# Sheet1.net
KiCad netlist of a schematic drawn in Altium Designer
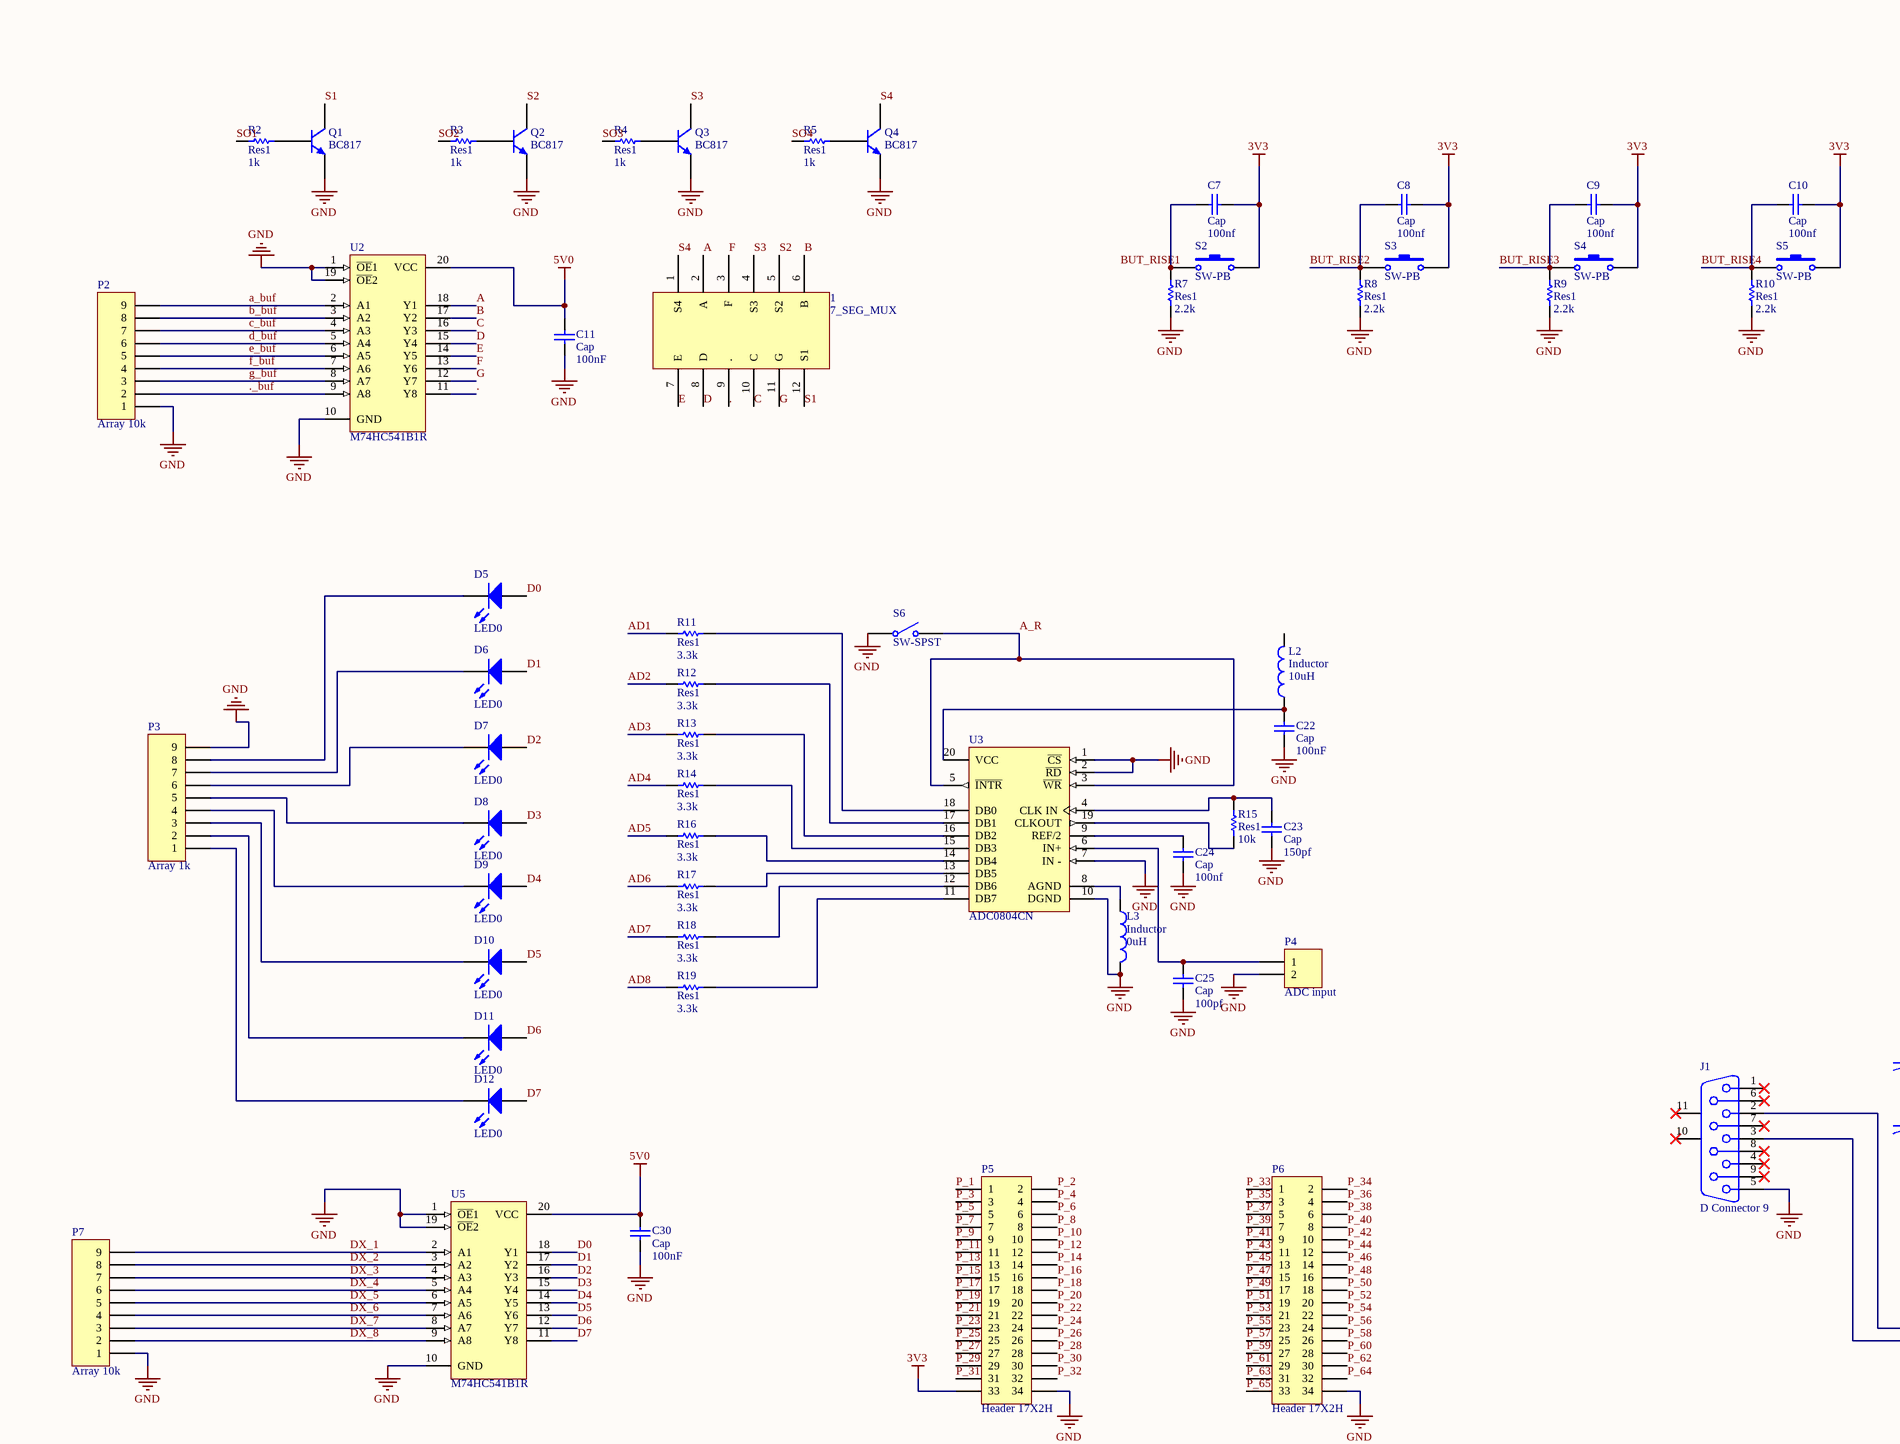
[diagram p0: Sheet1.SchDoc, top left]
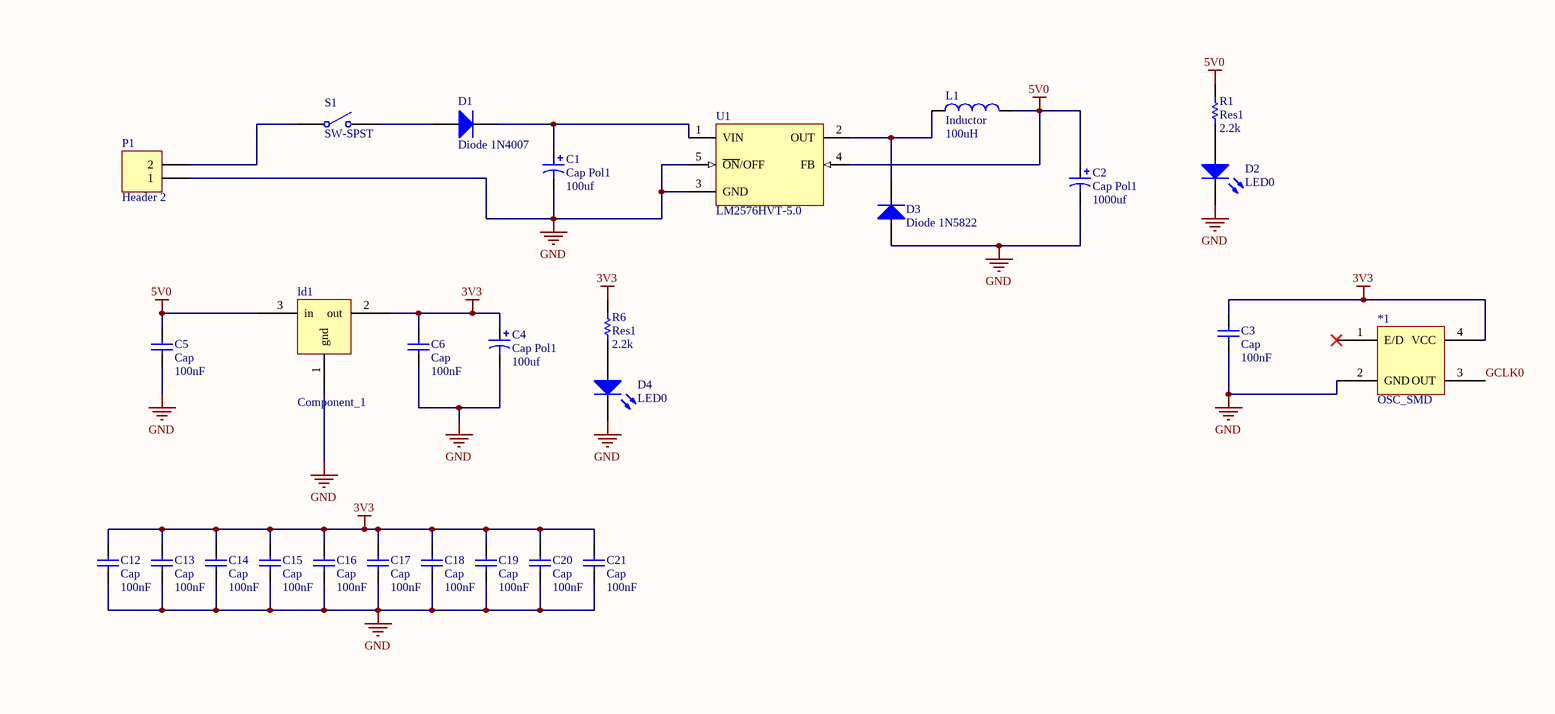
[diagram p1: Sheet1.SchDoc, top right]
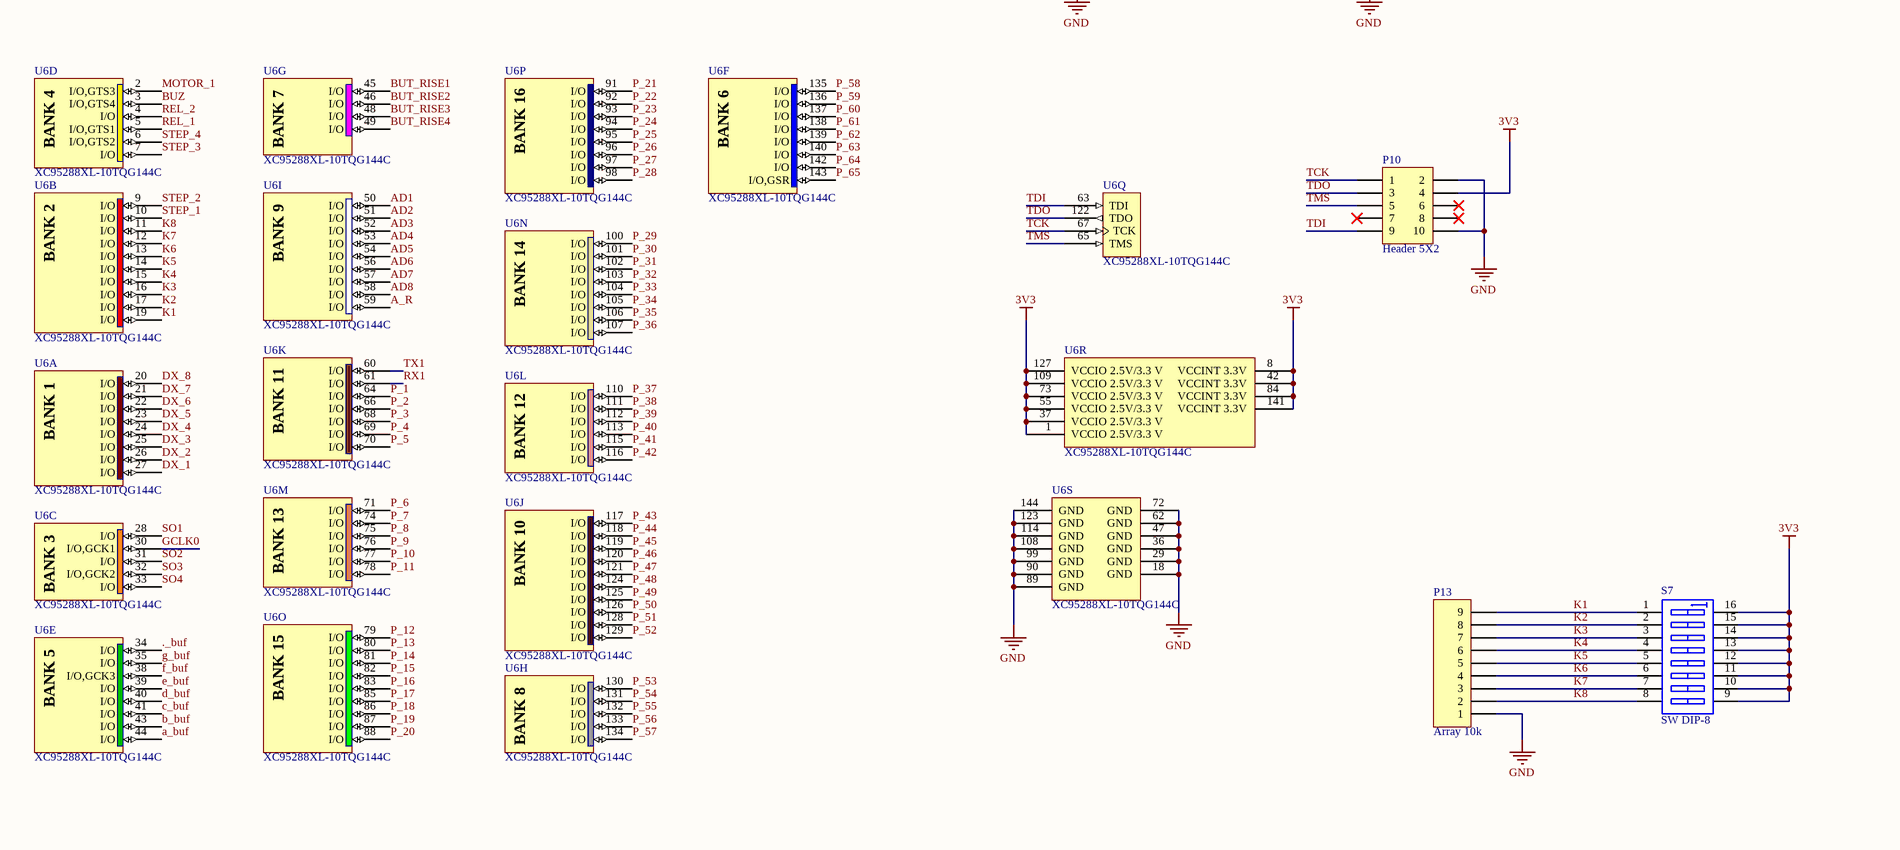
[diagram p2: Sheet1.SchDoc, bottom left]
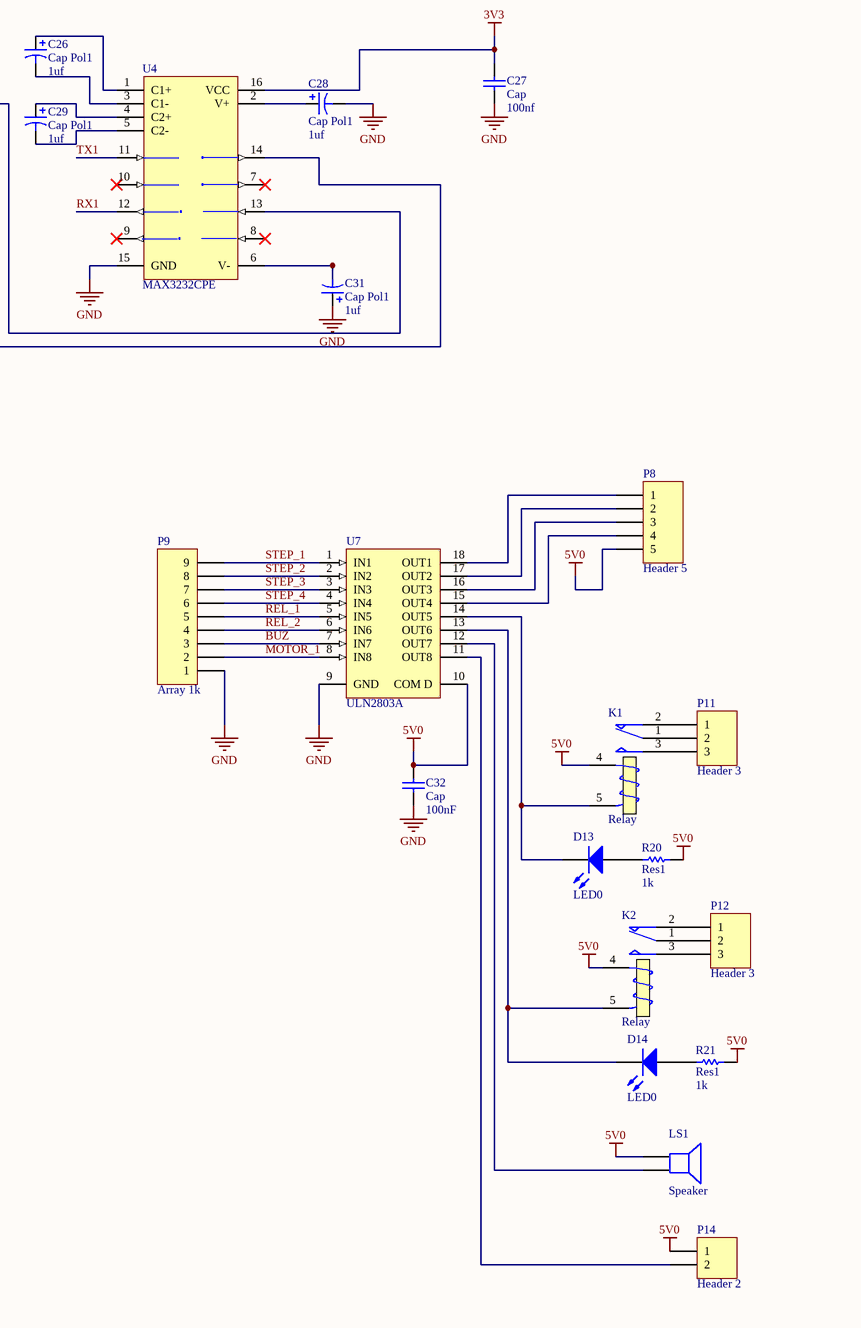
[diagram p3: Sheet1.SchDoc, bottom right]

(export (version "E")
  (design (tool "Eeschema 10.0.6"))
  (components
    (comp (ref "*1") (value "OSC_SMD") (footprint "osc_smd") (libsource (lib "OSC_SMD") (part "Component_1")))
    (comp (ref "1")
      (value "7_SEG_MUX")
      (footprint "s7_mux")
      (libsource (lib "7_SEG_MUX") (part "Component_1"))
    )
    (comp (ref "C1")
      (value "Cap Pol1")
      (footprint "C_CYL_SMD2")
      (description "Polarized Capacitor (Radial)")
      (fields (field (name "ALTIUM_VALUE") "100uf") (field (name "PUBLISHER") "Altium Limited"))
      (libsource (lib "Miscellaneous Devices") (part "Cap Pol1"))
    )
    (comp (ref "C2")
      (value "Cap Pol1")
      (footprint "C_CYL_SMD")
      (description "Polarized Capacitor (Radial)")
      (fields (field (name "ALTIUM_VALUE") "1000uf") (field (name "PUBLISHER") "Altium Limited"))
      (libsource (lib "Miscellaneous Devices") (part "Cap Pol1"))
    )
    (comp (ref "C3")
      (value "Cap")
      (footprint "SMD_805")
      (description "Capacitor")
      (fields (field (name "ALTIUM_VALUE") "100nF") (field (name "PUBLISHER") "Altium Limited"))
      (libsource (lib "Miscellaneous Devices") (part "Cap"))
    )
    (comp (ref "C4")
      (value "Cap Pol1")
      (footprint "C_B")
      (description "Polarized Capacitor (Radial)")
      (fields (field (name "ALTIUM_VALUE") "100uf") (field (name "PUBLISHER") "Altium Limited"))
      (libsource (lib "Miscellaneous Devices") (part "Cap Pol1"))
    )
    (comp (ref "C5")
      (value "Cap")
      (footprint "SMD_805")
      (description "Capacitor")
      (fields (field (name "ALTIUM_VALUE") "100nF") (field (name "PUBLISHER") "Altium Limited"))
      (libsource (lib "Miscellaneous Devices") (part "Cap"))
    )
    (comp (ref "C6")
      (value "Cap")
      (footprint "SMD_805")
      (description "Capacitor")
      (fields (field (name "ALTIUM_VALUE") "100nF") (field (name "PUBLISHER") "Altium Limited"))
      (libsource (lib "Miscellaneous Devices") (part "Cap"))
    )
    (comp (ref "C7")
      (value "Cap")
      (footprint "SMD_805")
      (description "Capacitor")
      (fields (field (name "ALTIUM_VALUE") "100nf") (field (name "PUBLISHER") "Altium Limited"))
      (libsource (lib "Miscellaneous Devices") (part "Cap"))
    )
    (comp (ref "C8")
      (value "Cap")
      (footprint "SMD_805")
      (description "Capacitor")
      (fields (field (name "ALTIUM_VALUE") "100nf") (field (name "PUBLISHER") "Altium Limited"))
      (libsource (lib "Miscellaneous Devices") (part "Cap"))
    )
    (comp (ref "C9")
      (value "Cap")
      (footprint "SMD_805")
      (description "Capacitor")
      (fields (field (name "ALTIUM_VALUE") "100nf") (field (name "PUBLISHER") "Altium Limited"))
      (libsource (lib "Miscellaneous Devices") (part "Cap"))
    )
    (comp (ref "C10")
      (value "Cap")
      (footprint "SMD_805")
      (description "Capacitor")
      (fields (field (name "ALTIUM_VALUE") "100nf") (field (name "PUBLISHER") "Altium Limited"))
      (libsource (lib "Miscellaneous Devices") (part "Cap"))
    )
    (comp (ref "C11")
      (value "Cap")
      (footprint "SMD_805")
      (description "Capacitor")
      (fields (field (name "ALTIUM_VALUE") "100nF") (field (name "PUBLISHER") "Altium Limited"))
      (libsource (lib "Miscellaneous Devices") (part "Cap"))
    )
    (comp (ref "C12")
      (value "Cap")
      (footprint "SMD_805")
      (description "Capacitor")
      (fields (field (name "ALTIUM_VALUE") "100nF") (field (name "PUBLISHER") "Altium Limited"))
      (libsource (lib "Miscellaneous Devices") (part "Cap"))
    )
    (comp (ref "C13")
      (value "Cap")
      (footprint "SMD_805")
      (description "Capacitor")
      (fields (field (name "ALTIUM_VALUE") "100nF") (field (name "PUBLISHER") "Altium Limited"))
      (libsource (lib "Miscellaneous Devices") (part "Cap"))
    )
    (comp (ref "C14")
      (value "Cap")
      (footprint "SMD_805")
      (description "Capacitor")
      (fields (field (name "ALTIUM_VALUE") "100nF") (field (name "PUBLISHER") "Altium Limited"))
      (libsource (lib "Miscellaneous Devices") (part "Cap"))
    )
    (comp (ref "C15")
      (value "Cap")
      (footprint "SMD_805")
      (description "Capacitor")
      (fields (field (name "ALTIUM_VALUE") "100nF") (field (name "PUBLISHER") "Altium Limited"))
      (libsource (lib "Miscellaneous Devices") (part "Cap"))
    )
    (comp (ref "C16")
      (value "Cap")
      (footprint "SMD_805")
      (description "Capacitor")
      (fields (field (name "ALTIUM_VALUE") "100nF") (field (name "PUBLISHER") "Altium Limited"))
      (libsource (lib "Miscellaneous Devices") (part "Cap"))
    )
    (comp (ref "C17")
      (value "Cap")
      (footprint "SMD_805")
      (description "Capacitor")
      (fields (field (name "ALTIUM_VALUE") "100nF") (field (name "PUBLISHER") "Altium Limited"))
      (libsource (lib "Miscellaneous Devices") (part "Cap"))
    )
    (comp (ref "C18")
      (value "Cap")
      (footprint "SMD_805")
      (description "Capacitor")
      (fields (field (name "ALTIUM_VALUE") "100nF") (field (name "PUBLISHER") "Altium Limited"))
      (libsource (lib "Miscellaneous Devices") (part "Cap"))
    )
    (comp (ref "C19")
      (value "Cap")
      (footprint "SMD_805")
      (description "Capacitor")
      (fields (field (name "ALTIUM_VALUE") "100nF") (field (name "PUBLISHER") "Altium Limited"))
      (libsource (lib "Miscellaneous Devices") (part "Cap"))
    )
    (comp (ref "C20")
      (value "Cap")
      (footprint "SMD_805")
      (description "Capacitor")
      (fields (field (name "ALTIUM_VALUE") "100nF") (field (name "PUBLISHER") "Altium Limited"))
      (libsource (lib "Miscellaneous Devices") (part "Cap"))
    )
    (comp (ref "C21")
      (value "Cap")
      (footprint "SMD_805")
      (description "Capacitor")
      (fields (field (name "ALTIUM_VALUE") "100nF") (field (name "PUBLISHER") "Altium Limited"))
      (libsource (lib "Miscellaneous Devices") (part "Cap"))
    )
    (comp (ref "C22")
      (value "Cap")
      (footprint "SMD_805")
      (description "Capacitor")
      (fields (field (name "ALTIUM_VALUE") "100nF") (field (name "PUBLISHER") "Altium Limited"))
      (libsource (lib "Miscellaneous Devices") (part "Cap"))
    )
    (comp (ref "C23")
      (value "Cap")
      (footprint "SMD_805")
      (description "Capacitor")
      (fields (field (name "ALTIUM_VALUE") "150pf") (field (name "PUBLISHER") "Altium Limited"))
      (libsource (lib "Miscellaneous Devices") (part "Cap"))
    )
    (comp (ref "C24")
      (value "Cap")
      (footprint "SMD_805")
      (description "Capacitor")
      (fields (field (name "ALTIUM_VALUE") "100nf") (field (name "PUBLISHER") "Altium Limited"))
      (libsource (lib "Miscellaneous Devices") (part "Cap"))
    )
    (comp (ref "C25")
      (value "Cap")
      (footprint "SMD_805")
      (description "Capacitor")
      (fields (field (name "ALTIUM_VALUE") "100pf") (field (name "PUBLISHER") "Altium Limited"))
      (libsource (lib "Miscellaneous Devices") (part "Cap"))
    )
    (comp (ref "C26")
      (value "Cap Pol1")
      (footprint "c_b")
      (description "Polarized Capacitor (Radial)")
      (fields (field (name "ALTIUM_VALUE") "1uf") (field (name "PUBLISHER") "Altium Limited"))
      (libsource (lib "Miscellaneous Devices") (part "Cap Pol1"))
    )
    (comp (ref "C27")
      (value "Cap")
      (footprint "SMD_805")
      (description "Capacitor")
      (fields (field (name "ALTIUM_VALUE") "100nf") (field (name "PUBLISHER") "Altium Limited"))
      (libsource (lib "Miscellaneous Devices") (part "Cap"))
    )
    (comp (ref "C28")
      (value "Cap Pol1")
      (footprint "c_b")
      (description "Polarized Capacitor (Radial)")
      (fields (field (name "ALTIUM_VALUE") "1uf") (field (name "PUBLISHER") "Altium Limited"))
      (libsource (lib "Miscellaneous Devices") (part "Cap Pol1"))
    )
    (comp (ref "C29")
      (value "Cap Pol1")
      (footprint "c_b")
      (description "Polarized Capacitor (Radial)")
      (fields (field (name "ALTIUM_VALUE") "1uf") (field (name "PUBLISHER") "Altium Limited"))
      (libsource (lib "Miscellaneous Devices") (part "Cap Pol1"))
    )
    (comp (ref "C30")
      (value "Cap")
      (footprint "SMD_805")
      (description "Capacitor")
      (fields (field (name "ALTIUM_VALUE") "100nF") (field (name "PUBLISHER") "Altium Limited"))
      (libsource (lib "Miscellaneous Devices") (part "Cap"))
    )
    (comp (ref "C31")
      (value "Cap Pol1")
      (footprint "c_b")
      (description "Polarized Capacitor (Radial)")
      (fields (field (name "ALTIUM_VALUE") "1uf") (field (name "PUBLISHER") "Altium Limited"))
      (libsource (lib "") (part "Cap Pol1_1"))
    )
    (comp (ref "C32")
      (value "Cap")
      (footprint "SMD_805")
      (description "Capacitor")
      (fields (field (name "ALTIUM_VALUE") "100nF") (field (name "PUBLISHER") "Altium Limited"))
      (libsource (lib "Miscellaneous Devices") (part "Cap"))
    )
    (comp (ref "D1")
      (value "Diode 1N4007")
      (footprint "TVS")
      (description "1 Amp General Purpose Rectifier")
      (fields (field (name "PUBLISHER") "Altium Limited"))
      (libsource (lib "Miscellaneous Devices") (part "Diode 1N4007"))
    )
    (comp (ref "D2")
      (value "LED0")
      (footprint "SMD_805")
      (description "Typical INFRARED GaAs LED")
      (fields (field (name "PUBLISHER") "Altium Limited"))
      (libsource (lib "Miscellaneous Devices") (part "LED0"))
    )
    (comp (ref "D3")
      (value "Diode 1N5822")
      (footprint "1N5822")
      (description "1 Amp General Purpose Rectifier")
      (fields (field (name "PUBLISHER") "Altium Limited"))
      (libsource (lib "Miscellaneous Devices") (part "Diode 1N4007"))
    )
    (comp (ref "D4")
      (value "LED0")
      (footprint "SMD_805")
      (description "Typical INFRARED GaAs LED")
      (fields (field (name "PUBLISHER") "Altium Limited"))
      (libsource (lib "Miscellaneous Devices") (part "LED0"))
    )
    (comp (ref "D5")
      (value "LED0")
      (footprint "SMD_805")
      (description "Typical INFRARED GaAs LED")
      (fields (field (name "PUBLISHER") "Altium Limited"))
      (libsource (lib "Miscellaneous Devices") (part "LED0"))
    )
    (comp (ref "D6")
      (value "LED0")
      (footprint "SMD_805")
      (description "Typical INFRARED GaAs LED")
      (fields (field (name "PUBLISHER") "Altium Limited"))
      (libsource (lib "Miscellaneous Devices") (part "LED0"))
    )
    (comp (ref "D7")
      (value "LED0")
      (footprint "SMD_805")
      (description "Typical INFRARED GaAs LED")
      (fields (field (name "PUBLISHER") "Altium Limited"))
      (libsource (lib "Miscellaneous Devices") (part "LED0"))
    )
    (comp (ref "D8")
      (value "LED0")
      (footprint "SMD_805")
      (description "Typical INFRARED GaAs LED")
      (fields (field (name "PUBLISHER") "Altium Limited"))
      (libsource (lib "Miscellaneous Devices") (part "LED0"))
    )
    (comp (ref "D9")
      (value "LED0")
      (footprint "SMD_805")
      (description "Typical INFRARED GaAs LED")
      (fields (field (name "PUBLISHER") "Altium Limited"))
      (libsource (lib "Miscellaneous Devices") (part "LED0"))
    )
    (comp (ref "D10")
      (value "LED0")
      (footprint "SMD_805")
      (description "Typical INFRARED GaAs LED")
      (fields (field (name "PUBLISHER") "Altium Limited"))
      (libsource (lib "Miscellaneous Devices") (part "LED0"))
    )
    (comp (ref "D11")
      (value "LED0")
      (footprint "SMD_805")
      (description "Typical INFRARED GaAs LED")
      (fields (field (name "PUBLISHER") "Altium Limited"))
      (libsource (lib "Miscellaneous Devices") (part "LED0"))
    )
    (comp (ref "D12")
      (value "LED0")
      (footprint "SMD_805")
      (description "Typical INFRARED GaAs LED")
      (fields (field (name "PUBLISHER") "Altium Limited"))
      (libsource (lib "Miscellaneous Devices") (part "LED0"))
    )
    (comp (ref "D13")
      (value "LED0")
      (footprint "SMD_805")
      (description "Typical INFRARED GaAs LED")
      (fields (field (name "PUBLISHER") "Altium Limited"))
      (libsource (lib "Miscellaneous Devices") (part "LED0"))
    )
    (comp (ref "D14")
      (value "LED0")
      (footprint "SMD_805")
      (description "Typical INFRARED GaAs LED")
      (fields (field (name "PUBLISHER") "Altium Limited"))
      (libsource (lib "Miscellaneous Devices") (part "LED0"))
    )
    (comp (ref "J1")
      (value "D Connector 9")
      (footprint "com")
      (description "Receptacle Assembly, 9 Position, Right Angle")
      (fields (field (name "PUBLISHER") "Altium Limited"))
      (libsource (lib "Miscellaneous Connectors") (part "D Connector 9"))
    )
    (comp (ref "K1")
      (value "Relay")
      (footprint "relay_5v")
      (description "SPDT Relay")
      (fields (field (name "PUBLISHER") "Altium Limited"))
      (libsource (lib "Miscellaneous Devices") (part "Relay"))
    )
    (comp (ref "K2")
      (value "Relay")
      (footprint "relay_5v")
      (description "SPDT Relay")
      (fields (field (name "PUBLISHER") "Altium Limited"))
      (libsource (lib "Miscellaneous Devices") (part "Relay"))
    )
    (comp (ref "L1")
      (value "Inductor")
      (footprint "INDUC_SMD")
      (fields (field (name "ALTIUM_VALUE") "100uH") (field (name "PUBLISHER") "Altium Limited"))
      (libsource (lib "Miscellaneous Devices") (part "Inductor"))
    )
    (comp (ref "L2")
      (value "Inductor")
      (footprint "SMD_805")
      (fields (field (name "ALTIUM_VALUE") "10uH") (field (name "PUBLISHER") "Altium Limited"))
      (libsource (lib "Miscellaneous Devices") (part "Inductor"))
    )
    (comp (ref "L3")
      (value "Inductor")
      (footprint "SMD_805")
      (fields (field (name "ALTIUM_VALUE") "0uH") (field (name "PUBLISHER") "Altium Limited"))
      (libsource (lib "Miscellaneous Devices") (part "Inductor"))
    )
    (comp (ref "ld1")
      (value "Component_1")
      (footprint "SOT223")
      (libsource (lib "lm1117") (part "Component_1"))
    )
    (comp (ref "LS1")
      (value "Speaker")
      (footprint "buzzer")
      (description "Loudspeaker")
      (fields (field (name "PUBLISHER") "Altium Limited"))
      (libsource (lib "Miscellaneous Devices") (part "Speaker"))
    )
    (comp (ref "P1")
      (value "Header 2")
      (footprint "ADAP_JACK")
      (description "Header, 2-Pin")
      (fields (field (name "PUBLISHER") "Altium Limited"))
      (libsource (lib "Miscellaneous Connectors") (part "Header 2"))
    )
    (comp (ref "P2")
      (value "Array 10k")
      (footprint "aray 9")
      (description "Header, 9-Pin, Right Angle")
      (fields (field (name "PUBLISHER") "Altium Limited"))
      (libsource (lib "Miscellaneous Connectors") (part "Header 9H"))
    )
    (comp (ref "P3")
      (value "Array 1k")
      (footprint "Aray 9")
      (description "Header, 9-Pin, Right Angle")
      (fields (field (name "PUBLISHER") "Altium Limited"))
      (libsource (lib "Miscellaneous Connectors") (part "Header 9H"))
    )
    (comp (ref "P4")
      (value "ADC input")
      (footprint "pin_2_w")
      (description "Header, 2-Pin")
      (fields (field (name "PUBLISHER") "Altium Limited"))
      (libsource (lib "") (part "Header 2_1"))
    )
    (comp (ref "P5")
      (value "Header 17X2H")
      (footprint "HDR2X17H")
      (description "Header, 17-Pin, Dual row, Right Angle")
      (fields (field (name "PUBLISHER") "Altium Limited"))
      (libsource (lib "Miscellaneous Connectors") (part "Header 17X2H"))
    )
    (comp (ref "P6")
      (value "Header 17X2H")
      (footprint "HDR2X17H")
      (description "Header, 17-Pin, Dual row, Right Angle")
      (fields (field (name "PUBLISHER") "Altium Limited"))
      (libsource (lib "Miscellaneous Connectors") (part "Header 17X2H"))
    )
    (comp (ref "P7")
      (value "Array 10k")
      (footprint "aray 9")
      (description "Header, 9-Pin, Right Angle")
      (fields (field (name "PUBLISHER") "Altium Limited"))
      (libsource (lib "Miscellaneous Connectors") (part "Header 9H"))
    )
    (comp (ref "P8")
      (value "Header 5")
      (footprint "pin_5_w")
      (description "Header, 5-Pin")
      (fields (field (name "PUBLISHER") "Altium Limited"))
      (libsource (lib "Miscellaneous Connectors") (part "Header 5"))
    )
    (comp (ref "P9")
      (value "Array 1k")
      (footprint "aray 9")
      (description "Header, 9-Pin, Right Angle")
      (fields (field (name "PUBLISHER") "Altium Limited"))
      (libsource (lib "Miscellaneous Connectors") (part "Header 9H"))
    )
    (comp (ref "P10")
      (value "Header 5X2")
      (footprint "box2x5_3d")
      (description "Header, 5-Pin, Dual row")
      (fields (field (name "PUBLISHER") "Altium Limited"))
      (libsource (lib "Miscellaneous Connectors") (part "Header 5X2"))
    )
    (comp (ref "P11")
      (value "Header 3")
      (footprint "pin_3_w")
      (description "Header, 3-Pin")
      (fields (field (name "PUBLISHER") "Altium Limited"))
      (libsource (lib "Miscellaneous Connectors") (part "Header 3"))
    )
    (comp (ref "P12")
      (value "Header 3")
      (footprint "pin_3_w")
      (description "Header, 3-Pin")
      (fields (field (name "PUBLISHER") "Altium Limited"))
      (libsource (lib "Miscellaneous Connectors") (part "Header 3"))
    )
    (comp (ref "P13")
      (value "Array 10k")
      (footprint "aray 9")
      (description "Header, 9-Pin, Right Angle")
      (fields (field (name "PUBLISHER") "Altium Limited"))
      (libsource (lib "Miscellaneous Connectors") (part "Header 9H"))
    )
    (comp (ref "P14")
      (value "Header 2")
      (footprint "pin_2_w")
      (description "Header, 2-Pin")
      (fields (field (name "PUBLISHER") "Altium Limited"))
      (libsource (lib "") (part "Header 2_1"))
    )
    (comp (ref "Q1")
      (value "BC817")
      (footprint "sot23")
      (description "NPN General Purpose Amplifier")
      (fields (field (name "PUBLISHER") "Altium Limited"))
      (libsource (lib "Miscellaneous Devices") (part "2N3904"))
    )
    (comp (ref "Q2")
      (value "BC817")
      (footprint "sot23")
      (description "NPN General Purpose Amplifier")
      (fields (field (name "PUBLISHER") "Altium Limited"))
      (libsource (lib "Miscellaneous Devices") (part "2N3904"))
    )
    (comp (ref "Q3")
      (value "BC817")
      (footprint "sot23")
      (description "NPN General Purpose Amplifier")
      (fields (field (name "PUBLISHER") "Altium Limited"))
      (libsource (lib "Miscellaneous Devices") (part "2N3904"))
    )
    (comp (ref "Q4")
      (value "BC817")
      (footprint "sot23")
      (description "NPN General Purpose Amplifier")
      (fields (field (name "PUBLISHER") "Altium Limited"))
      (libsource (lib "Miscellaneous Devices") (part "2N3904"))
    )
    (comp (ref "R1")
      (value "Res1")
      (footprint "SMD_805")
      (description "Resistor")
      (fields (field (name "ALTIUM_VALUE") "2.2k") (field (name "PUBLISHER") "Altium Limited"))
      (libsource (lib "Miscellaneous Devices") (part "Res1"))
    )
    (comp (ref "R2")
      (value "Res1")
      (footprint "SMD_805")
      (description "Resistor")
      (fields (field (name "ALTIUM_VALUE") "1k") (field (name "PUBLISHER") "Altium Limited"))
      (libsource (lib "Miscellaneous Devices") (part "Res1"))
    )
    (comp (ref "R3")
      (value "Res1")
      (footprint "SMD_805")
      (description "Resistor")
      (fields (field (name "ALTIUM_VALUE") "1k") (field (name "PUBLISHER") "Altium Limited"))
      (libsource (lib "Miscellaneous Devices") (part "Res1"))
    )
    (comp (ref "R4")
      (value "Res1")
      (footprint "SMD_805")
      (description "Resistor")
      (fields (field (name "ALTIUM_VALUE") "1k") (field (name "PUBLISHER") "Altium Limited"))
      (libsource (lib "Miscellaneous Devices") (part "Res1"))
    )
    (comp (ref "R5")
      (value "Res1")
      (footprint "SMD_805")
      (description "Resistor")
      (fields (field (name "ALTIUM_VALUE") "1k") (field (name "PUBLISHER") "Altium Limited"))
      (libsource (lib "Miscellaneous Devices") (part "Res1"))
    )
    (comp (ref "R6")
      (value "Res1")
      (footprint "SMD_805")
      (description "Resistor")
      (fields (field (name "ALTIUM_VALUE") "2.2k") (field (name "PUBLISHER") "Altium Limited"))
      (libsource (lib "Miscellaneous Devices") (part "Res1"))
    )
    (comp (ref "R7")
      (value "Res1")
      (footprint "SMD_805")
      (description "Resistor")
      (fields (field (name "ALTIUM_VALUE") "2.2k") (field (name "PUBLISHER") "Altium Limited"))
      (libsource (lib "Miscellaneous Devices") (part "Res1"))
    )
    (comp (ref "R8")
      (value "Res1")
      (footprint "SMD_805")
      (description "Resistor")
      (fields (field (name "ALTIUM_VALUE") "2.2k") (field (name "PUBLISHER") "Altium Limited"))
      (libsource (lib "Miscellaneous Devices") (part "Res1"))
    )
    (comp (ref "R9")
      (value "Res1")
      (footprint "SMD_805")
      (description "Resistor")
      (fields (field (name "ALTIUM_VALUE") "2.2k") (field (name "PUBLISHER") "Altium Limited"))
      (libsource (lib "Miscellaneous Devices") (part "Res1"))
    )
    (comp (ref "R10")
      (value "Res1")
      (footprint "SMD_805")
      (description "Resistor")
      (fields (field (name "ALTIUM_VALUE") "2.2k") (field (name "PUBLISHER") "Altium Limited"))
      (libsource (lib "Miscellaneous Devices") (part "Res1"))
    )
    (comp (ref "R11")
      (value "Res1")
      (footprint "SMD_805")
      (description "Resistor")
      (fields (field (name "ALTIUM_VALUE") "3.3k") (field (name "PUBLISHER") "Altium Limited"))
      (libsource (lib "Miscellaneous Devices") (part "Res1"))
    )
    (comp (ref "R12")
      (value "Res1")
      (footprint "SMD_805")
      (description "Resistor")
      (fields (field (name "ALTIUM_VALUE") "3.3k") (field (name "PUBLISHER") "Altium Limited"))
      (libsource (lib "Miscellaneous Devices") (part "Res1"))
    )
    (comp (ref "R13")
      (value "Res1")
      (footprint "SMD_805")
      (description "Resistor")
      (fields (field (name "ALTIUM_VALUE") "3.3k") (field (name "PUBLISHER") "Altium Limited"))
      (libsource (lib "Miscellaneous Devices") (part "Res1"))
    )
    (comp (ref "R14")
      (value "Res1")
      (footprint "SMD_805")
      (description "Resistor")
      (fields (field (name "ALTIUM_VALUE") "3.3k") (field (name "PUBLISHER") "Altium Limited"))
      (libsource (lib "Miscellaneous Devices") (part "Res1"))
    )
    (comp (ref "R15")
      (value "Res1")
      (footprint "SMD_805")
      (description "Resistor")
      (fields (field (name "ALTIUM_VALUE") "10k") (field (name "PUBLISHER") "Altium Limited"))
      (libsource (lib "Miscellaneous Devices") (part "Res1"))
    )
    (comp (ref "R16")
      (value "Res1")
      (footprint "SMD_805")
      (description "Resistor")
      (fields (field (name "ALTIUM_VALUE") "3.3k") (field (name "PUBLISHER") "Altium Limited"))
      (libsource (lib "Miscellaneous Devices") (part "Res1"))
    )
    (comp (ref "R17")
      (value "Res1")
      (footprint "SMD_805")
      (description "Resistor")
      (fields (field (name "ALTIUM_VALUE") "3.3k") (field (name "PUBLISHER") "Altium Limited"))
      (libsource (lib "Miscellaneous Devices") (part "Res1"))
    )
    (comp (ref "R18")
      (value "Res1")
      (footprint "SMD_805")
      (description "Resistor")
      (fields (field (name "ALTIUM_VALUE") "3.3k") (field (name "PUBLISHER") "Altium Limited"))
      (libsource (lib "Miscellaneous Devices") (part "Res1"))
    )
    (comp (ref "R19")
      (value "Res1")
      (footprint "SMD_805")
      (description "Resistor")
      (fields (field (name "ALTIUM_VALUE") "3.3k") (field (name "PUBLISHER") "Altium Limited"))
      (libsource (lib "Miscellaneous Devices") (part "Res1"))
    )
    (comp (ref "R20")
      (value "Res1")
      (footprint "SMD_805")
      (description "Resistor")
      (fields (field (name "ALTIUM_VALUE") "1k") (field (name "PUBLISHER") "Altium Limited"))
      (libsource (lib "Miscellaneous Devices") (part "Res1"))
    )
    (comp (ref "R21")
      (value "Res1")
      (footprint "SMD_805")
      (description "Resistor")
      (fields (field (name "ALTIUM_VALUE") "1k") (field (name "PUBLISHER") "Altium Limited"))
      (libsource (lib "Miscellaneous Devices") (part "Res1"))
    )
    (comp (ref "S1")
      (value "SW-SPST")
      (footprint "KEY1")
      (description "Single-Pole, Single-Throw Switch")
      (fields (field (name "PUBLISHER") "Altium Limited"))
      (libsource (lib "Miscellaneous Devices") (part "SW-SPST"))
    )
    (comp (ref "S2")
      (value "SW-PB")
      (footprint "res_b")
      (description "Switch")
      (fields (field (name "PUBLISHER") "Altium Limited"))
      (libsource (lib "Miscellaneous Devices") (part "SW-PB"))
    )
    (comp (ref "S3")
      (value "SW-PB")
      (footprint "res_b")
      (description "Switch")
      (fields (field (name "PUBLISHER") "Altium Limited"))
      (libsource (lib "Miscellaneous Devices") (part "SW-PB"))
    )
    (comp (ref "S4")
      (value "SW-PB")
      (footprint "res_b")
      (description "Switch")
      (fields (field (name "PUBLISHER") "Altium Limited"))
      (libsource (lib "Miscellaneous Devices") (part "SW-PB"))
    )
    (comp (ref "S5")
      (value "SW-PB")
      (footprint "res_b")
      (description "Switch")
      (fields (field (name "PUBLISHER") "Altium Limited"))
      (libsource (lib "Miscellaneous Devices") (part "SW-PB"))
    )
    (comp (ref "S6")
      (value "SW-SPST")
      (footprint "key1")
      (description "Single-Pole, Single-Throw Switch")
      (fields (field (name "PUBLISHER") "Altium Limited"))
      (libsource (lib "Miscellaneous Devices") (part "SW-SPST"))
    )
    (comp (ref "S7")
      (value "SW DIP-8")
      (footprint "array_key8")
      (description "DIP Switch, 8 Position, SPST")
      (fields (field (name "PUBLISHER") "Altium Limited"))
      (libsource (lib "Miscellaneous Devices") (part "SW DIP-8"))
    )
    (comp (ref "U1")
      (value "LM2576HVT-5.0")
      (footprint "LM2576_SMD")
      (description "SIMPLE SWITCHER; 3A Step-Down Voltage Regulator")
      (fields
        (field (name "MANUFACTURER") "National Semiconductor")
        (field (name "DIGIKEYPARTNUMBER") "LM2576HVT-5.0-ND")
        (field (name "PUBLISHER") "Altium Limited")
      )
      (libsource (lib "NSC Switcher") (part "LM2576HVT-5.0"))
    )
    (comp (ref "U2")
      (value "M74HC541B1R")
      (footprint "sop20")
      (description "Octal Bus Buffer with 3 State Outputs (Non Inverted)")
      (fields (field (name "PUBLISHER") "Altium Limited"))
      (libsource (lib "ST Logic Buffer Line Driver") (part "M74HC541B1R"))
    )
    (comp (ref "U3")
      (value "ADC0804CN")
      (footprint "DIp_20p")
      (description "8-Bit Analog-to-Digital Converter with Differential Inputs")
      (fields (field (name "PUBLISHER") "Altium Limited"))
      (libsource (lib "TI Converter Analog to Digital") (part "ADC0804CN"))
    )
    (comp (ref "U4")
      (value "MAX3232CPE")
      (footprint "sop16")
      (description "3.0V TO 5.5V, Low-Power, up to 1Mbps, True RS-232 Transceiver Using Four 0.1µF External Capacitor")
      (fields (field (name "PUBLISHER") "Altium Limited"))
      (libsource (lib "Maxim Communication Transceiver") (part "MAX3232CPE"))
    )
    (comp (ref "U5")
      (value "M74HC541B1R")
      (footprint "sop20")
      (description "Octal Bus Buffer with 3 State Outputs (Non Inverted)")
      (fields (field (name "PUBLISHER") "Altium Limited"))
      (libsource (lib "ST Logic Buffer Line Driver") (part "M74HC541B1R"))
    )
    (comp (ref "U6")
      (value "XC95288XL-10TQG144C")
      (footprint "TQG144_N")
      (fields (field (name "PUBLISHER") "Altium Limited"))
      (libsource (lib "Xilinx PLD XC9500XL") (part "XC95288XL-10TQG144C"))
    )
    (comp (ref "U7")
      (value "ULN2803A")
      (footprint "sol18")
      (description "High-Voltage, High-Current Darlington Array")
      (fields (field (name "PUBLISHER") "Altium Limited"))
      (libsource (lib "Allegro Interface Darlington Driver") (part "ULN2803A"))
    )
  )
  (nets
    (net (code "1") (name "/.") (class "Default")
      (node (ref "1") (pin "9") (pinfunction "._9") (pintype "passive"))
      (node (ref "U2") (pin "11") (pinfunction "Y8_11") (pintype "tri_state"))
    )
    (net (code "2") (name "/._buf") (class "Default")
      (node (ref "P2") (pin "2") (pinfunction "2_2") (pintype "passive"))
      (node (ref "U2") (pin "9") (pinfunction "A8_9") (pintype "input"))
      (node (ref "U6") (pin "34") (pinfunction "I/O_34") (pintype "bidirectional"))
    )
    (net (code "3") (name "/A") (class "Default")
      (node (ref "1") (pin "2") (pinfunction "A_2") (pintype "passive"))
      (node (ref "U2") (pin "18") (pinfunction "Y1_18") (pintype "tri_state"))
    )
    (net (code "4") (name "/AD1") (class "Default")
      (node (ref "R11") (pin "1") (pinfunction "1_1") (pintype "passive"))
      (node (ref "U6") (pin "50") (pinfunction "I/O_50") (pintype "bidirectional"))
    )
    (net (code "5") (name "/AD2") (class "Default")
      (node (ref "R12") (pin "1") (pinfunction "1_1") (pintype "passive"))
      (node (ref "U6") (pin "51") (pinfunction "I/O_51") (pintype "bidirectional"))
    )
    (net (code "6") (name "/AD3") (class "Default")
      (node (ref "R13") (pin "1") (pinfunction "1_1") (pintype "passive"))
      (node (ref "U6") (pin "52") (pinfunction "I/O_52") (pintype "bidirectional"))
    )
    (net (code "7") (name "/AD4") (class "Default")
      (node (ref "R14") (pin "1") (pinfunction "1_1") (pintype "passive"))
      (node (ref "U6") (pin "53") (pinfunction "I/O_53") (pintype "bidirectional"))
    )
    (net (code "8") (name "/AD5") (class "Default")
      (node (ref "R16") (pin "1") (pinfunction "1_1") (pintype "passive"))
      (node (ref "U6") (pin "54") (pinfunction "I/O_54") (pintype "bidirectional"))
    )
    (net (code "9") (name "/AD6") (class "Default")
      (node (ref "R17") (pin "1") (pinfunction "1_1") (pintype "passive"))
      (node (ref "U6") (pin "56") (pinfunction "I/O_56") (pintype "bidirectional"))
    )
    (net (code "10") (name "/AD7") (class "Default")
      (node (ref "R18") (pin "1") (pinfunction "1_1") (pintype "passive"))
      (node (ref "U6") (pin "57") (pinfunction "I/O_57") (pintype "bidirectional"))
    )
    (net (code "11") (name "/AD8") (class "Default")
      (node (ref "R19") (pin "1") (pinfunction "1_1") (pintype "passive"))
      (node (ref "U6") (pin "58") (pinfunction "I/O_58") (pintype "bidirectional"))
    )
    (net (code "12") (name "/A_R") (class "Default")
      (node (ref "S6") (pin "2") (pinfunction "NO_2") (pintype "passive"))
      (node (ref "U3") (pin "3") (pinfunction "~{WR}_3") (pintype "input"))
      (node (ref "U3") (pin "5") (pinfunction "~{INTR}_5") (pintype "output"))
      (node (ref "U6") (pin "59") (pinfunction "I/O_59") (pintype "bidirectional"))
    )
    (net (code "13") (name "/B") (class "Default")
      (node (ref "1") (pin "6") (pinfunction "B_6") (pintype "passive"))
      (node (ref "U2") (pin "17") (pinfunction "Y2_17") (pintype "tri_state"))
    )
    (net (code "14") (name "/BUT_RISE1") (class "Default")
      (node (ref "U6") (pin "45") (pinfunction "I/O_45") (pintype "bidirectional"))
    )
    (net (code "15") (name "/BUT_RISE2") (class "Default")
      (node (ref "C8") (pin "1") (pinfunction "1_1") (pintype "passive"))
      (node (ref "R8") (pin "1") (pinfunction "1_1") (pintype "passive"))
      (node (ref "S3") (pin "1") (pinfunction "1_1") (pintype "passive"))
      (node (ref "U6") (pin "46") (pinfunction "I/O_46") (pintype "bidirectional"))
    )
    (net (code "16") (name "/BUT_RISE3") (class "Default")
      (node (ref "C9") (pin "1") (pinfunction "1_1") (pintype "passive"))
      (node (ref "R9") (pin "1") (pinfunction "1_1") (pintype "passive"))
      (node (ref "S4") (pin "1") (pinfunction "1_1") (pintype "passive"))
      (node (ref "U6") (pin "48") (pinfunction "I/O_48") (pintype "bidirectional"))
    )
    (net (code "17") (name "/BUT_RISE4") (class "Default")
      (node (ref "C10") (pin "1") (pinfunction "1_1") (pintype "passive"))
      (node (ref "R10") (pin "1") (pinfunction "1_1") (pintype "passive"))
      (node (ref "S5") (pin "1") (pinfunction "1_1") (pintype "passive"))
      (node (ref "U6") (pin "49") (pinfunction "I/O_49") (pintype "bidirectional"))
    )
    (net (code "18") (name "/BUZ") (class "Default")
      (node (ref "P9") (pin "3") (pinfunction "3_3") (pintype "passive"))
      (node (ref "U6") (pin "3") (pinfunction "I/O,GTS4_3") (pintype "bidirectional"))
      (node (ref "U7") (pin "7") (pinfunction "IN7_7") (pintype "input"))
    )
    (net (code "19") (name "/C") (class "Default")
      (node (ref "1") (pin "10") (pinfunction "C_10") (pintype "passive"))
      (node (ref "U2") (pin "16") (pinfunction "Y3_16") (pintype "tri_state"))
    )
    (net (code "20") (name "/D") (class "Default")
      (node (ref "1") (pin "8") (pinfunction "D_8") (pintype "passive"))
      (node (ref "U2") (pin "15") (pinfunction "Y4_15") (pintype "tri_state"))
    )
    (net (code "21") (name "/D0") (class "Default")
      (node (ref "D5") (pin "1") (pinfunction "A_1") (pintype "passive"))
      (node (ref "U5") (pin "18") (pinfunction "Y1_18") (pintype "tri_state"))
    )
    (net (code "22") (name "/D1") (class "Default")
      (node (ref "D6") (pin "1") (pinfunction "A_1") (pintype "passive"))
      (node (ref "U5") (pin "17") (pinfunction "Y2_17") (pintype "tri_state"))
    )
    (net (code "23") (name "/D2") (class "Default")
      (node (ref "D7") (pin "1") (pinfunction "A_1") (pintype "passive"))
      (node (ref "U5") (pin "16") (pinfunction "Y3_16") (pintype "tri_state"))
    )
    (net (code "24") (name "/D3") (class "Default")
      (node (ref "D8") (pin "1") (pinfunction "A_1") (pintype "passive"))
      (node (ref "U5") (pin "15") (pinfunction "Y4_15") (pintype "tri_state"))
    )
    (net (code "25") (name "/D4") (class "Default")
      (node (ref "D9") (pin "1") (pinfunction "A_1") (pintype "passive"))
      (node (ref "U5") (pin "14") (pinfunction "Y5_14") (pintype "tri_state"))
    )
    (net (code "26") (name "/D5") (class "Default")
      (node (ref "D10") (pin "1") (pinfunction "A_1") (pintype "passive"))
      (node (ref "U5") (pin "13") (pinfunction "Y6_13") (pintype "tri_state"))
    )
    (net (code "27") (name "/D6") (class "Default")
      (node (ref "D11") (pin "1") (pinfunction "A_1") (pintype "passive"))
      (node (ref "U5") (pin "12") (pinfunction "Y7_12") (pintype "tri_state"))
    )
    (net (code "28") (name "/D7") (class "Default")
      (node (ref "D12") (pin "1") (pinfunction "A_1") (pintype "passive"))
      (node (ref "U5") (pin "11") (pinfunction "Y8_11") (pintype "tri_state"))
    )
    (net (code "29") (name "/DX_1") (class "Default")
      (node (ref "P7") (pin "9") (pinfunction "9_9") (pintype "passive"))
      (node (ref "U5") (pin "2") (pinfunction "A1_2") (pintype "input"))
      (node (ref "U6") (pin "27") (pinfunction "I/O_27") (pintype "bidirectional"))
    )
    (net (code "30") (name "/DX_2") (class "Default")
      (node (ref "P7") (pin "8") (pinfunction "8_8") (pintype "passive"))
      (node (ref "U5") (pin "3") (pinfunction "A2_3") (pintype "input"))
      (node (ref "U6") (pin "26") (pinfunction "I/O_26") (pintype "bidirectional"))
    )
    (net (code "31") (name "/DX_3") (class "Default")
      (node (ref "P7") (pin "7") (pinfunction "7_7") (pintype "passive"))
      (node (ref "U5") (pin "4") (pinfunction "A3_4") (pintype "input"))
      (node (ref "U6") (pin "25") (pinfunction "I/O_25") (pintype "bidirectional"))
    )
    (net (code "32") (name "/DX_4") (class "Default")
      (node (ref "P7") (pin "6") (pinfunction "6_6") (pintype "passive"))
      (node (ref "U5") (pin "5") (pinfunction "A4_5") (pintype "input"))
      (node (ref "U6") (pin "24") (pinfunction "I/O_24") (pintype "bidirectional"))
    )
    (net (code "33") (name "/DX_5") (class "Default")
      (node (ref "P7") (pin "5") (pinfunction "5_5") (pintype "passive"))
      (node (ref "U5") (pin "6") (pinfunction "A5_6") (pintype "input"))
      (node (ref "U6") (pin "23") (pinfunction "I/O_23") (pintype "bidirectional"))
    )
    (net (code "34") (name "/DX_6") (class "Default")
      (node (ref "P7") (pin "4") (pinfunction "4_4") (pintype "passive"))
      (node (ref "U5") (pin "7") (pinfunction "A6_7") (pintype "input"))
      (node (ref "U6") (pin "22") (pinfunction "I/O_22") (pintype "bidirectional"))
    )
    (net (code "35") (name "/DX_7") (class "Default")
      (node (ref "P7") (pin "3") (pinfunction "3_3") (pintype "passive"))
      (node (ref "U5") (pin "8") (pinfunction "A7_8") (pintype "input"))
      (node (ref "U6") (pin "21") (pinfunction "I/O_21") (pintype "bidirectional"))
    )
    (net (code "36") (name "/DX_8") (class "Default")
      (node (ref "P7") (pin "2") (pinfunction "2_2") (pintype "passive"))
      (node (ref "U5") (pin "9") (pinfunction "A8_9") (pintype "input"))
      (node (ref "U6") (pin "20") (pinfunction "I/O_20") (pintype "bidirectional"))
    )
    (net (code "37") (name "/E") (class "Default")
      (node (ref "1") (pin "7") (pinfunction "E_7") (pintype "passive"))
      (node (ref "U2") (pin "14") (pinfunction "Y5_14") (pintype "tri_state"))
    )
    (net (code "38") (name "/F") (class "Default")
      (node (ref "1") (pin "3") (pinfunction "F_3") (pintype "passive"))
      (node (ref "U2") (pin "13") (pinfunction "Y6_13") (pintype "tri_state"))
    )
    (net (code "39") (name "/G") (class "Default")
      (node (ref "1") (pin "11") (pinfunction "G_11") (pintype "passive"))
      (node (ref "U2") (pin "12") (pinfunction "Y7_12") (pintype "tri_state"))
    )
    (net (code "40") (name "/GCLK0") (class "Default")
      (node (ref "*1") (pin "3") (pinfunction "OUT_3") (pintype "passive"))
      (node (ref "U6") (pin "30") (pinfunction "I/O,GCK1_30") (pintype "bidirectional"))
    )
    (net (code "41") (name "/K1") (class "Default")
      (node (ref "P13") (pin "9") (pinfunction "9_9") (pintype "passive"))
      (node (ref "S7") (pin "1") (pinfunction "A1_1") (pintype "passive"))
      (node (ref "U6") (pin "19") (pinfunction "I/O_19") (pintype "bidirectional"))
    )
    (net (code "42") (name "/K2") (class "Default")
      (node (ref "P13") (pin "8") (pinfunction "8_8") (pintype "passive"))
      (node (ref "S7") (pin "2") (pinfunction "A2_2") (pintype "passive"))
      (node (ref "U6") (pin "17") (pinfunction "I/O_17") (pintype "bidirectional"))
    )
    (net (code "43") (name "/K3") (class "Default")
      (node (ref "P13") (pin "7") (pinfunction "7_7") (pintype "passive"))
      (node (ref "S7") (pin "3") (pinfunction "A3_3") (pintype "passive"))
      (node (ref "U6") (pin "16") (pinfunction "I/O_16") (pintype "bidirectional"))
    )
    (net (code "44") (name "/K4") (class "Default")
      (node (ref "P13") (pin "6") (pinfunction "6_6") (pintype "passive"))
      (node (ref "S7") (pin "4") (pinfunction "A4_4") (pintype "passive"))
      (node (ref "U6") (pin "15") (pinfunction "I/O_15") (pintype "bidirectional"))
    )
    (net (code "45") (name "/K5") (class "Default")
      (node (ref "P13") (pin "5") (pinfunction "5_5") (pintype "passive"))
      (node (ref "S7") (pin "5") (pinfunction "A5_5") (pintype "passive"))
      (node (ref "U6") (pin "14") (pinfunction "I/O_14") (pintype "bidirectional"))
    )
    (net (code "46") (name "/K6") (class "Default")
      (node (ref "P13") (pin "4") (pinfunction "4_4") (pintype "passive"))
      (node (ref "S7") (pin "6") (pinfunction "A6_6") (pintype "passive"))
      (node (ref "U6") (pin "13") (pinfunction "I/O_13") (pintype "bidirectional"))
    )
    (net (code "47") (name "/K7") (class "Default")
      (node (ref "P13") (pin "3") (pinfunction "3_3") (pintype "passive"))
      (node (ref "S7") (pin "7") (pinfunction "A7_7") (pintype "passive"))
      (node (ref "U6") (pin "12") (pinfunction "I/O_12") (pintype "bidirectional"))
    )
    (net (code "48") (name "/K8") (class "Default")
      (node (ref "P13") (pin "2") (pinfunction "2_2") (pintype "passive"))
      (node (ref "S7") (pin "8") (pinfunction "A8_8") (pintype "passive"))
      (node (ref "U6") (pin "11") (pinfunction "I/O_11") (pintype "bidirectional"))
    )
    (net (code "49") (name "/MOTOR_1") (class "Default")
      (node (ref "P9") (pin "2") (pinfunction "2_2") (pintype "passive"))
      (node (ref "U6") (pin "2") (pinfunction "I/O,GTS3_2") (pintype "bidirectional"))
      (node (ref "U7") (pin "8") (pinfunction "IN8_8") (pintype "input"))
    )
    (net (code "50") (name "/P_1") (class "Default")
      (node (ref "P5") (pin "1") (pinfunction "1_1") (pintype "passive"))
      (node (ref "U6") (pin "64") (pinfunction "I/O_64") (pintype "bidirectional"))
    )
    (net (code "51") (name "/P_2") (class "Default")
      (node (ref "P5") (pin "2") (pinfunction "2_2") (pintype "passive"))
      (node (ref "U6") (pin "66") (pinfunction "I/O_66") (pintype "bidirectional"))
    )
    (net (code "52") (name "/P_3") (class "Default")
      (node (ref "P5") (pin "3") (pinfunction "3_3") (pintype "passive"))
      (node (ref "U6") (pin "68") (pinfunction "I/O_68") (pintype "bidirectional"))
    )
    (net (code "53") (name "/P_4") (class "Default")
      (node (ref "P5") (pin "4") (pinfunction "4_4") (pintype "passive"))
      (node (ref "U6") (pin "69") (pinfunction "I/O_69") (pintype "bidirectional"))
    )
    (net (code "54") (name "/P_5") (class "Default")
      (node (ref "P5") (pin "5") (pinfunction "5_5") (pintype "passive"))
      (node (ref "U6") (pin "70") (pinfunction "I/O_70") (pintype "bidirectional"))
    )
    (net (code "55") (name "/P_6") (class "Default")
      (node (ref "P5") (pin "6") (pinfunction "6_6") (pintype "passive"))
      (node (ref "U6") (pin "71") (pinfunction "I/O_71") (pintype "bidirectional"))
    )
    (net (code "56") (name "/P_7") (class "Default")
      (node (ref "P5") (pin "7") (pinfunction "7_7") (pintype "passive"))
      (node (ref "U6") (pin "74") (pinfunction "I/O_74") (pintype "bidirectional"))
    )
    (net (code "57") (name "/P_8") (class "Default")
      (node (ref "P5") (pin "8") (pinfunction "8_8") (pintype "passive"))
      (node (ref "U6") (pin "75") (pinfunction "I/O_75") (pintype "bidirectional"))
    )
    (net (code "58") (name "/P_9") (class "Default")
      (node (ref "P5") (pin "9") (pinfunction "9_9") (pintype "passive"))
      (node (ref "U6") (pin "76") (pinfunction "I/O_76") (pintype "bidirectional"))
    )
    (net (code "59") (name "/P_10") (class "Default")
      (node (ref "P5") (pin "10") (pinfunction "10_10") (pintype "passive"))
      (node (ref "U6") (pin "77") (pinfunction "I/O_77") (pintype "bidirectional"))
    )
    (net (code "60") (name "/P_11") (class "Default")
      (node (ref "P5") (pin "11") (pinfunction "11_11") (pintype "passive"))
      (node (ref "U6") (pin "78") (pinfunction "I/O_78") (pintype "bidirectional"))
    )
    (net (code "61") (name "/P_12") (class "Default")
      (node (ref "P5") (pin "12") (pinfunction "12_12") (pintype "passive"))
      (node (ref "U6") (pin "79") (pinfunction "I/O_79") (pintype "bidirectional"))
    )
    (net (code "62") (name "/P_13") (class "Default")
      (node (ref "P5") (pin "13") (pinfunction "13_13") (pintype "passive"))
      (node (ref "U6") (pin "80") (pinfunction "I/O_80") (pintype "bidirectional"))
    )
    (net (code "63") (name "/P_14") (class "Default")
      (node (ref "P5") (pin "14") (pinfunction "14_14") (pintype "passive"))
      (node (ref "U6") (pin "81") (pinfunction "I/O_81") (pintype "bidirectional"))
    )
    (net (code "64") (name "/P_15") (class "Default")
      (node (ref "P5") (pin "15") (pinfunction "15_15") (pintype "passive"))
      (node (ref "U6") (pin "82") (pinfunction "I/O_82") (pintype "bidirectional"))
    )
    (net (code "65") (name "/P_16") (class "Default")
      (node (ref "P5") (pin "16") (pinfunction "16_16") (pintype "passive"))
      (node (ref "U6") (pin "83") (pinfunction "I/O_83") (pintype "bidirectional"))
    )
    (net (code "66") (name "/P_17") (class "Default")
      (node (ref "P5") (pin "17") (pinfunction "17_17") (pintype "passive"))
      (node (ref "U6") (pin "85") (pinfunction "I/O_85") (pintype "bidirectional"))
    )
    (net (code "67") (name "/P_18") (class "Default")
      (node (ref "P5") (pin "18") (pinfunction "18_18") (pintype "passive"))
      (node (ref "U6") (pin "86") (pinfunction "I/O_86") (pintype "bidirectional"))
    )
    (net (code "68") (name "/P_19") (class "Default")
      (node (ref "P5") (pin "19") (pinfunction "19_19") (pintype "passive"))
      (node (ref "U6") (pin "87") (pinfunction "I/O_87") (pintype "bidirectional"))
    )
    (net (code "69") (name "/P_20") (class "Default")
      (node (ref "P5") (pin "20") (pinfunction "20_20") (pintype "passive"))
      (node (ref "U6") (pin "88") (pinfunction "I/O_88") (pintype "bidirectional"))
    )
    (net (code "70") (name "/P_21") (class "Default")
      (node (ref "P5") (pin "21") (pinfunction "21_21") (pintype "passive"))
      (node (ref "U6") (pin "91") (pinfunction "I/O_91") (pintype "bidirectional"))
    )
    (net (code "71") (name "/P_22") (class "Default")
      (node (ref "P5") (pin "22") (pinfunction "22_22") (pintype "passive"))
      (node (ref "U6") (pin "92") (pinfunction "I/O_92") (pintype "bidirectional"))
    )
    (net (code "72") (name "/P_23") (class "Default")
      (node (ref "P5") (pin "23") (pinfunction "23_23") (pintype "passive"))
      (node (ref "U6") (pin "93") (pinfunction "I/O_93") (pintype "bidirectional"))
    )
    (net (code "73") (name "/P_24") (class "Default")
      (node (ref "P5") (pin "24") (pinfunction "24_24") (pintype "passive"))
      (node (ref "U6") (pin "94") (pinfunction "I/O_94") (pintype "bidirectional"))
    )
    (net (code "74") (name "/P_25") (class "Default")
      (node (ref "P5") (pin "25") (pinfunction "25_25") (pintype "passive"))
      (node (ref "U6") (pin "95") (pinfunction "I/O_95") (pintype "bidirectional"))
    )
    (net (code "75") (name "/P_26") (class "Default")
      (node (ref "P5") (pin "26") (pinfunction "26_26") (pintype "passive"))
      (node (ref "U6") (pin "96") (pinfunction "I/O_96") (pintype "bidirectional"))
    )
    (net (code "76") (name "/P_27") (class "Default")
      (node (ref "P5") (pin "27") (pinfunction "27_27") (pintype "passive"))
      (node (ref "U6") (pin "97") (pinfunction "I/O_97") (pintype "bidirectional"))
    )
    (net (code "77") (name "/P_28") (class "Default")
      (node (ref "P5") (pin "28") (pinfunction "28_28") (pintype "passive"))
      (node (ref "U6") (pin "98") (pinfunction "I/O_98") (pintype "bidirectional"))
    )
    (net (code "78") (name "/P_29") (class "Default")
      (node (ref "P5") (pin "29") (pinfunction "29_29") (pintype "passive"))
      (node (ref "U6") (pin "100") (pinfunction "I/O_100") (pintype "bidirectional"))
    )
    (net (code "79") (name "/P_30") (class "Default")
      (node (ref "P5") (pin "30") (pinfunction "30_30") (pintype "passive"))
      (node (ref "U6") (pin "101") (pinfunction "I/O_101") (pintype "bidirectional"))
    )
    (net (code "80") (name "/P_31") (class "Default")
      (node (ref "P5") (pin "31") (pinfunction "31_31") (pintype "passive"))
      (node (ref "U6") (pin "102") (pinfunction "I/O_102") (pintype "bidirectional"))
    )
    (net (code "81") (name "/P_32") (class "Default")
      (node (ref "P5") (pin "32") (pinfunction "32_32") (pintype "passive"))
      (node (ref "U6") (pin "103") (pinfunction "I/O_103") (pintype "bidirectional"))
    )
    (net (code "82") (name "/P_33") (class "Default")
      (node (ref "P6") (pin "1") (pinfunction "1_1") (pintype "passive"))
      (node (ref "U6") (pin "104") (pinfunction "I/O_104") (pintype "bidirectional"))
    )
    (net (code "83") (name "/P_34") (class "Default")
      (node (ref "P6") (pin "2") (pinfunction "2_2") (pintype "passive"))
      (node (ref "U6") (pin "105") (pinfunction "I/O_105") (pintype "bidirectional"))
    )
    (net (code "84") (name "/P_35") (class "Default")
      (node (ref "P6") (pin "3") (pinfunction "3_3") (pintype "passive"))
      (node (ref "U6") (pin "106") (pinfunction "I/O_106") (pintype "bidirectional"))
    )
    (net (code "85") (name "/P_36") (class "Default")
      (node (ref "P6") (pin "4") (pinfunction "4_4") (pintype "passive"))
      (node (ref "U6") (pin "107") (pinfunction "I/O_107") (pintype "bidirectional"))
    )
    (net (code "86") (name "/P_37") (class "Default")
      (node (ref "P6") (pin "5") (pinfunction "5_5") (pintype "passive"))
      (node (ref "U6") (pin "110") (pinfunction "I/O_110") (pintype "bidirectional"))
    )
    (net (code "87") (name "/P_38") (class "Default")
      (node (ref "P6") (pin "6") (pinfunction "6_6") (pintype "passive"))
      (node (ref "U6") (pin "111") (pinfunction "I/O_111") (pintype "bidirectional"))
    )
    (net (code "88") (name "/P_39") (class "Default")
      (node (ref "P6") (pin "7") (pinfunction "7_7") (pintype "passive"))
      (node (ref "U6") (pin "112") (pinfunction "I/O_112") (pintype "bidirectional"))
    )
    (net (code "89") (name "/P_40") (class "Default")
      (node (ref "P6") (pin "8") (pinfunction "8_8") (pintype "passive"))
      (node (ref "U6") (pin "113") (pinfunction "I/O_113") (pintype "bidirectional"))
    )
    (net (code "90") (name "/P_41") (class "Default")
      (node (ref "P6") (pin "9") (pinfunction "9_9") (pintype "passive"))
      (node (ref "U6") (pin "115") (pinfunction "I/O_115") (pintype "bidirectional"))
    )
    (net (code "91") (name "/P_42") (class "Default")
      (node (ref "P6") (pin "10") (pinfunction "10_10") (pintype "passive"))
      (node (ref "U6") (pin "116") (pinfunction "I/O_116") (pintype "bidirectional"))
    )
    (net (code "92") (name "/P_43") (class "Default")
      (node (ref "P6") (pin "11") (pinfunction "11_11") (pintype "passive"))
      (node (ref "U6") (pin "117") (pinfunction "I/O_117") (pintype "bidirectional"))
    )
    (net (code "93") (name "/P_44") (class "Default")
      (node (ref "P6") (pin "12") (pinfunction "12_12") (pintype "passive"))
      (node (ref "U6") (pin "118") (pinfunction "I/O_118") (pintype "bidirectional"))
    )
    (net (code "94") (name "/P_45") (class "Default")
      (node (ref "P6") (pin "13") (pinfunction "13_13") (pintype "passive"))
      (node (ref "U6") (pin "119") (pinfunction "I/O_119") (pintype "bidirectional"))
    )
    (net (code "95") (name "/P_46") (class "Default")
      (node (ref "P6") (pin "14") (pinfunction "14_14") (pintype "passive"))
      (node (ref "U6") (pin "120") (pinfunction "I/O_120") (pintype "bidirectional"))
    )
    (net (code "96") (name "/P_47") (class "Default")
      (node (ref "P6") (pin "15") (pinfunction "15_15") (pintype "passive"))
      (node (ref "U6") (pin "121") (pinfunction "I/O_121") (pintype "bidirectional"))
    )
    (net (code "97") (name "/P_48") (class "Default")
      (node (ref "P6") (pin "16") (pinfunction "16_16") (pintype "passive"))
      (node (ref "U6") (pin "124") (pinfunction "I/O_124") (pintype "bidirectional"))
    )
    (net (code "98") (name "/P_49") (class "Default")
      (node (ref "P6") (pin "17") (pinfunction "17_17") (pintype "passive"))
      (node (ref "U6") (pin "125") (pinfunction "I/O_125") (pintype "bidirectional"))
    )
    (net (code "99") (name "/P_50") (class "Default")
      (node (ref "P6") (pin "18") (pinfunction "18_18") (pintype "passive"))
      (node (ref "U6") (pin "126") (pinfunction "I/O_126") (pintype "bidirectional"))
    )
    (net (code "100") (name "/P_51") (class "Default")
      (node (ref "P6") (pin "19") (pinfunction "19_19") (pintype "passive"))
      (node (ref "U6") (pin "128") (pinfunction "I/O_128") (pintype "bidirectional"))
    )
    (net (code "101") (name "/P_52") (class "Default")
      (node (ref "P6") (pin "20") (pinfunction "20_20") (pintype "passive"))
      (node (ref "U6") (pin "129") (pinfunction "I/O_129") (pintype "bidirectional"))
    )
    (net (code "102") (name "/P_53") (class "Default")
      (node (ref "P6") (pin "21") (pinfunction "21_21") (pintype "passive"))
      (node (ref "U6") (pin "130") (pinfunction "I/O_130") (pintype "bidirectional"))
    )
    (net (code "103") (name "/P_54") (class "Default")
      (node (ref "P6") (pin "22") (pinfunction "22_22") (pintype "passive"))
      (node (ref "U6") (pin "131") (pinfunction "I/O_131") (pintype "bidirectional"))
    )
    (net (code "104") (name "/P_55") (class "Default")
      (node (ref "P6") (pin "23") (pinfunction "23_23") (pintype "passive"))
      (node (ref "U6") (pin "132") (pinfunction "I/O_132") (pintype "bidirectional"))
    )
    (net (code "105") (name "/P_56") (class "Default")
      (node (ref "P6") (pin "24") (pinfunction "24_24") (pintype "passive"))
      (node (ref "U6") (pin "133") (pinfunction "I/O_133") (pintype "bidirectional"))
    )
    (net (code "106") (name "/P_57") (class "Default")
      (node (ref "P6") (pin "25") (pinfunction "25_25") (pintype "passive"))
      (node (ref "U6") (pin "134") (pinfunction "I/O_134") (pintype "bidirectional"))
    )
    (net (code "107") (name "/P_58") (class "Default")
      (node (ref "P6") (pin "26") (pinfunction "26_26") (pintype "passive"))
      (node (ref "U6") (pin "135") (pinfunction "I/O_135") (pintype "bidirectional"))
    )
    (net (code "108") (name "/P_59") (class "Default")
      (node (ref "P6") (pin "27") (pinfunction "27_27") (pintype "passive"))
      (node (ref "U6") (pin "136") (pinfunction "I/O_136") (pintype "bidirectional"))
    )
    (net (code "109") (name "/P_60") (class "Default")
      (node (ref "P6") (pin "28") (pinfunction "28_28") (pintype "passive"))
      (node (ref "U6") (pin "137") (pinfunction "I/O_137") (pintype "bidirectional"))
    )
    (net (code "110") (name "/P_61") (class "Default")
      (node (ref "P6") (pin "29") (pinfunction "29_29") (pintype "passive"))
      (node (ref "U6") (pin "138") (pinfunction "I/O_138") (pintype "bidirectional"))
    )
    (net (code "111") (name "/P_62") (class "Default")
      (node (ref "P6") (pin "30") (pinfunction "30_30") (pintype "passive"))
      (node (ref "U6") (pin "139") (pinfunction "I/O_139") (pintype "bidirectional"))
    )
    (net (code "112") (name "/P_63") (class "Default")
      (node (ref "P6") (pin "31") (pinfunction "31_31") (pintype "passive"))
      (node (ref "U6") (pin "140") (pinfunction "I/O_140") (pintype "bidirectional"))
    )
    (net (code "113") (name "/P_64") (class "Default")
      (node (ref "P6") (pin "32") (pinfunction "32_32") (pintype "passive"))
      (node (ref "U6") (pin "142") (pinfunction "I/O_142") (pintype "bidirectional"))
    )
    (net (code "114") (name "/P_65") (class "Default")
      (node (ref "P6") (pin "33") (pinfunction "33_33") (pintype "passive"))
      (node (ref "U6") (pin "143") (pinfunction "I/O,GSR_143") (pintype "bidirectional"))
    )
    (net (code "115") (name "/REL_1") (class "Default")
      (node (ref "P9") (pin "5") (pinfunction "5_5") (pintype "passive"))
      (node (ref "U6") (pin "5") (pinfunction "I/O,GTS1_5") (pintype "bidirectional"))
      (node (ref "U7") (pin "5") (pinfunction "IN5_5") (pintype "input"))
    )
    (net (code "116") (name "/REL_2") (class "Default")
      (node (ref "P9") (pin "4") (pinfunction "4_4") (pintype "passive"))
      (node (ref "U6") (pin "4") (pinfunction "I/O_4") (pintype "bidirectional"))
      (node (ref "U7") (pin "6") (pinfunction "IN6_6") (pintype "input"))
    )
    (net (code "117") (name "/RX1") (class "Default")
      (node (ref "U4") (pin "12") (pinfunction "R1OUT_12") (pintype "output"))
      (node (ref "U6") (pin "61") (pinfunction "I/O_61") (pintype "bidirectional"))
    )
    (net (code "118") (name "/S1") (class "Default")
      (node (ref "1") (pin "12") (pinfunction "S1_12") (pintype "passive"))
      (node (ref "Q1") (pin "3") (pinfunction "C_3") (pintype "passive"))
    )
    (net (code "119") (name "/S2") (class "Default")
      (node (ref "1") (pin "5") (pinfunction "S2_5") (pintype "passive"))
      (node (ref "Q2") (pin "3") (pinfunction "C_3") (pintype "passive"))
    )
    (net (code "120") (name "/S3") (class "Default")
      (node (ref "1") (pin "4") (pinfunction "S3_4") (pintype "passive"))
      (node (ref "Q3") (pin "3") (pinfunction "C_3") (pintype "passive"))
    )
    (net (code "121") (name "/S4") (class "Default")
      (node (ref "1") (pin "1") (pinfunction "S4_1") (pintype "passive"))
      (node (ref "Q4") (pin "3") (pinfunction "C_3") (pintype "passive"))
    )
    (net (code "122") (name "/SO1") (class "Default")
      (node (ref "R2") (pin "2") (pinfunction "2_2") (pintype "passive"))
      (node (ref "U6") (pin "28") (pinfunction "I/O_28") (pintype "bidirectional"))
    )
    (net (code "123") (name "/SO2") (class "Default")
      (node (ref "R3") (pin "2") (pinfunction "2_2") (pintype "passive"))
      (node (ref "U6") (pin "31") (pinfunction "I/O_31") (pintype "bidirectional"))
    )
    (net (code "124") (name "/SO3") (class "Default")
      (node (ref "R4") (pin "2") (pinfunction "2_2") (pintype "passive"))
      (node (ref "U6") (pin "32") (pinfunction "I/O,GCK2_32") (pintype "bidirectional"))
    )
    (net (code "125") (name "/SO4") (class "Default")
      (node (ref "R5") (pin "2") (pinfunction "2_2") (pintype "passive"))
      (node (ref "U6") (pin "33") (pinfunction "I/O_33") (pintype "bidirectional"))
    )
    (net (code "126") (name "/STEP_1") (class "Default")
      (node (ref "P9") (pin "9") (pinfunction "9_9") (pintype "passive"))
      (node (ref "U6") (pin "10") (pinfunction "I/O_10") (pintype "bidirectional"))
      (node (ref "U7") (pin "1") (pinfunction "IN1_1") (pintype "input"))
    )
    (net (code "127") (name "/STEP_2") (class "Default")
      (node (ref "P9") (pin "8") (pinfunction "8_8") (pintype "passive"))
      (node (ref "U6") (pin "9") (pinfunction "I/O_9") (pintype "bidirectional"))
      (node (ref "U7") (pin "2") (pinfunction "IN2_2") (pintype "input"))
    )
    (net (code "128") (name "/STEP_3") (class "Default")
      (node (ref "P9") (pin "7") (pinfunction "7_7") (pintype "passive"))
      (node (ref "U6") (pin "7") (pinfunction "I/O_7") (pintype "bidirectional"))
      (node (ref "U7") (pin "3") (pinfunction "IN3_3") (pintype "input"))
    )
    (net (code "129") (name "/STEP_4") (class "Default")
      (node (ref "P9") (pin "6") (pinfunction "6_6") (pintype "passive"))
      (node (ref "U6") (pin "6") (pinfunction "I/O,GTS2_6") (pintype "bidirectional"))
      (node (ref "U7") (pin "4") (pinfunction "IN4_4") (pintype "input"))
    )
    (net (code "130") (name "/TCK") (class "Default")
      (node (ref "P10") (pin "1") (pinfunction "1_1") (pintype "passive"))
      (node (ref "U6") (pin "67") (pinfunction "TCK_67") (pintype "input"))
    )
    (net (code "131") (name "/TDI") (class "Default")
      (node (ref "P10") (pin "9") (pinfunction "9_9") (pintype "passive"))
      (node (ref "U6") (pin "63") (pinfunction "TDI_63") (pintype "input"))
    )
    (net (code "132") (name "/TDO") (class "Default")
      (node (ref "P10") (pin "3") (pinfunction "3_3") (pintype "passive"))
      (node (ref "U6") (pin "122") (pinfunction "TDO_122") (pintype "output"))
    )
    (net (code "133") (name "/TMS") (class "Default")
      (node (ref "P10") (pin "5") (pinfunction "5_5") (pintype "passive"))
      (node (ref "U6") (pin "65") (pinfunction "TMS_65") (pintype "input"))
    )
    (net (code "134") (name "/TX1") (class "Default")
      (node (ref "U4") (pin "11") (pinfunction "T1IN_11") (pintype "input"))
      (node (ref "U6") (pin "60") (pinfunction "I/O_60") (pintype "bidirectional"))
    )
    (net (code "135") (name "/a_buf") (class "Default")
      (node (ref "P2") (pin "9") (pinfunction "9_9") (pintype "passive"))
      (node (ref "U2") (pin "2") (pinfunction "A1_2") (pintype "input"))
      (node (ref "U6") (pin "44") (pinfunction "I/O_44") (pintype "bidirectional"))
    )
    (net (code "136") (name "/b_buf") (class "Default")
      (node (ref "P2") (pin "8") (pinfunction "8_8") (pintype "passive"))
      (node (ref "U2") (pin "3") (pinfunction "A2_3") (pintype "input"))
      (node (ref "U6") (pin "43") (pinfunction "I/O_43") (pintype "bidirectional"))
    )
    (net (code "137") (name "/c_buf") (class "Default")
      (node (ref "P2") (pin "7") (pinfunction "7_7") (pintype "passive"))
      (node (ref "U2") (pin "4") (pinfunction "A3_4") (pintype "input"))
      (node (ref "U6") (pin "41") (pinfunction "I/O_41") (pintype "bidirectional"))
    )
    (net (code "138") (name "/d_buf") (class "Default")
      (node (ref "P2") (pin "6") (pinfunction "6_6") (pintype "passive"))
      (node (ref "U2") (pin "5") (pinfunction "A4_5") (pintype "input"))
      (node (ref "U6") (pin "40") (pinfunction "I/O_40") (pintype "bidirectional"))
    )
    (net (code "139") (name "/e_buf") (class "Default")
      (node (ref "P2") (pin "5") (pinfunction "5_5") (pintype "passive"))
      (node (ref "U2") (pin "6") (pinfunction "A5_6") (pintype "input"))
      (node (ref "U6") (pin "39") (pinfunction "I/O_39") (pintype "bidirectional"))
    )
    (net (code "140") (name "/f_buf") (class "Default")
      (node (ref "P2") (pin "4") (pinfunction "4_4") (pintype "passive"))
      (node (ref "U2") (pin "7") (pinfunction "A6_7") (pintype "input"))
      (node (ref "U6") (pin "38") (pinfunction "I/O,GCK3_38") (pintype "bidirectional"))
    )
    (net (code "141") (name "/g_buf") (class "Default")
      (node (ref "P2") (pin "3") (pinfunction "3_3") (pintype "passive"))
      (node (ref "U2") (pin "8") (pinfunction "A7_8") (pintype "input"))
      (node (ref "U6") (pin "35") (pinfunction "I/O_35") (pintype "bidirectional"))
    )
    (net (code "142") (name "3V3") (class "Default")
      (node (ref "*1") (pin "4") (pinfunction "VCC_4") (pintype "passive"))
      (node (ref "C10") (pin "2") (pinfunction "2_2") (pintype "passive"))
      (node (ref "C12") (pin "1") (pinfunction "1_1") (pintype "passive"))
      (node (ref "C13") (pin "1") (pinfunction "1_1") (pintype "passive"))
      (node (ref "C14") (pin "1") (pinfunction "1_1") (pintype "passive"))
      (node (ref "C15") (pin "1") (pinfunction "1_1") (pintype "passive"))
      (node (ref "C16") (pin "1") (pinfunction "1_1") (pintype "passive"))
      (node (ref "C17") (pin "1") (pinfunction "1_1") (pintype "passive"))
      (node (ref "C18") (pin "1") (pinfunction "1_1") (pintype "passive"))
      (node (ref "C19") (pin "1") (pinfunction "1_1") (pintype "passive"))
      (node (ref "C20") (pin "1") (pinfunction "1_1") (pintype "passive"))
      (node (ref "C21") (pin "1") (pinfunction "1_1") (pintype "passive"))
      (node (ref "C27") (pin "2") (pinfunction "2_2") (pintype "passive"))
      (node (ref "C3") (pin "1") (pinfunction "1_1") (pintype "passive"))
      (node (ref "C4") (pin "1") (pinfunction "1_1") (pintype "passive"))
      (node (ref "C6") (pin "1") (pinfunction "1_1") (pintype "passive"))
      (node (ref "C7") (pin "2") (pinfunction "2_2") (pintype "passive"))
      (node (ref "C8") (pin "2") (pinfunction "2_2") (pintype "passive"))
      (node (ref "C9") (pin "2") (pinfunction "2_2") (pintype "passive"))
      (node (ref "P10") (pin "4") (pinfunction "4_4") (pintype "passive"))
      (node (ref "P5") (pin "33") (pinfunction "33_33") (pintype "passive"))
      (node (ref "R6") (pin "2") (pinfunction "2_2") (pintype "passive"))
      (node (ref "S2") (pin "2") (pinfunction "2_2") (pintype "passive"))
      (node (ref "S3") (pin "2") (pinfunction "2_2") (pintype "passive"))
      (node (ref "S4") (pin "2") (pinfunction "2_2") (pintype "passive"))
      (node (ref "S5") (pin "2") (pinfunction "2_2") (pintype "passive"))
      (node (ref "S7") (pin "10") (pinfunction "B7_10") (pintype "passive"))
      (node (ref "S7") (pin "11") (pinfunction "B6_11") (pintype "passive"))
      (node (ref "S7") (pin "12") (pinfunction "B5_12") (pintype "passive"))
      (node (ref "S7") (pin "13") (pinfunction "B4_13") (pintype "passive"))
      (node (ref "S7") (pin "14") (pinfunction "B3_14") (pintype "passive"))
      (node (ref "S7") (pin "15") (pinfunction "B2_15") (pintype "passive"))
      (node (ref "S7") (pin "16") (pinfunction "B1_16") (pintype "passive"))
      (node (ref "S7") (pin "9") (pinfunction "B8_9") (pintype "passive"))
      (node (ref "U4") (pin "16") (pinfunction "VCC_16") (pintype "power_in"))
      (node (ref "U6") (pin "1") (pinfunction "VCCIO_2.5V/3.3_V_1") (pintype "power_in"))
      (node (ref "U6") (pin "109") (pinfunction "VCCIO_2.5V/3.3_V_109") (pintype "power_in"))
      (node (ref "U6") (pin "127") (pinfunction "VCCIO_2.5V/3.3_V_127") (pintype "power_in"))
      (node (ref "U6") (pin "141") (pinfunction "VCCINT_3.3V_141") (pintype "power_in"))
      (node (ref "U6") (pin "37") (pinfunction "VCCIO_2.5V/3.3_V_37") (pintype "power_in"))
      (node (ref "U6") (pin "42") (pinfunction "VCCINT_3.3V_42") (pintype "power_in"))
      (node (ref "U6") (pin "55") (pinfunction "VCCIO_2.5V/3.3_V_55") (pintype "power_in"))
      (node (ref "U6") (pin "73") (pinfunction "VCCIO_2.5V/3.3_V_73") (pintype "power_in"))
      (node (ref "U6") (pin "8") (pinfunction "VCCINT_3.3V_8") (pintype "power_in"))
      (node (ref "U6") (pin "84") (pinfunction "VCCINT_3.3V_84") (pintype "power_in"))
      (node (ref "ld1") (pin "2") (pinfunction "out_2") (pintype "passive"))
    )
    (net (code "143") (name "5V0") (class "Default")
      (node (ref "C11") (pin "1") (pinfunction "1_1") (pintype "passive"))
      (node (ref "C2") (pin "1") (pinfunction "1_1") (pintype "passive"))
      (node (ref "C30") (pin "1") (pinfunction "1_1") (pintype "passive"))
      (node (ref "C32") (pin "1") (pinfunction "1_1") (pintype "passive"))
      (node (ref "C5") (pin "1") (pinfunction "1_1") (pintype "passive"))
      (node (ref "K1") (pin "4") (pinfunction "T1_4") (pintype "passive"))
      (node (ref "K2") (pin "4") (pinfunction "T1_4") (pintype "passive"))
      (node (ref "L1") (pin "2") (pinfunction "2_2") (pintype "passive"))
      (node (ref "LS1") (pin "1") (pinfunction "1_1") (pintype "passive"))
      (node (ref "P14") (pin "1") (pinfunction "1_1") (pintype "passive"))
      (node (ref "P8") (pin "5") (pinfunction "5_5") (pintype "passive"))
      (node (ref "R1") (pin "2") (pinfunction "2_2") (pintype "passive"))
      (node (ref "R20") (pin "2") (pinfunction "2_2") (pintype "passive"))
      (node (ref "R21") (pin "2") (pinfunction "2_2") (pintype "passive"))
      (node (ref "U1") (pin "4") (pinfunction "FB_4") (pintype "input"))
      (node (ref "U2") (pin "20") (pinfunction "VCC_20") (pintype "power_in"))
      (node (ref "U5") (pin "20") (pinfunction "VCC_20") (pintype "power_in"))
      (node (ref "U7") (pin "10") (pinfunction "COM_D_10") (pintype "passive"))
      (node (ref "ld1") (pin "3") (pinfunction "in_3") (pintype "passive"))
    )
    (net (code "144") (name "GND") (class "Default")
      (node (ref "*1") (pin "2") (pinfunction "GND_2") (pintype "passive"))
      (node (ref "C1") (pin "2") (pinfunction "2_2") (pintype "passive"))
      (node (ref "C11") (pin "2") (pinfunction "2_2") (pintype "passive"))
      (node (ref "C12") (pin "2") (pinfunction "2_2") (pintype "passive"))
      (node (ref "C13") (pin "2") (pinfunction "2_2") (pintype "passive"))
      (node (ref "C14") (pin "2") (pinfunction "2_2") (pintype "passive"))
      (node (ref "C15") (pin "2") (pinfunction "2_2") (pintype "passive"))
      (node (ref "C16") (pin "2") (pinfunction "2_2") (pintype "passive"))
      (node (ref "C17") (pin "2") (pinfunction "2_2") (pintype "passive"))
      (node (ref "C18") (pin "2") (pinfunction "2_2") (pintype "passive"))
      (node (ref "C19") (pin "2") (pinfunction "2_2") (pintype "passive"))
      (node (ref "C2") (pin "2") (pinfunction "2_2") (pintype "passive"))
      (node (ref "C20") (pin "2") (pinfunction "2_2") (pintype "passive"))
      (node (ref "C21") (pin "2") (pinfunction "2_2") (pintype "passive"))
      (node (ref "C22") (pin "2") (pinfunction "2_2") (pintype "passive"))
      (node (ref "C23") (pin "2") (pinfunction "2_2") (pintype "passive"))
      (node (ref "C24") (pin "2") (pinfunction "2_2") (pintype "passive"))
      (node (ref "C25") (pin "2") (pinfunction "2_2") (pintype "passive"))
      (node (ref "C27") (pin "1") (pinfunction "1_1") (pintype "passive"))
      (node (ref "C28") (pin "2") (pinfunction "2_2") (pintype "passive"))
      (node (ref "C3") (pin "2") (pinfunction "2_2") (pintype "passive"))
      (node (ref "C30") (pin "2") (pinfunction "2_2") (pintype "passive"))
      (node (ref "C31") (pin "1") (pinfunction "1_1") (pintype "passive"))
      (node (ref "C32") (pin "2") (pinfunction "2_2") (pintype "passive"))
      (node (ref "C4") (pin "2") (pinfunction "2_2") (pintype "passive"))
      (node (ref "C5") (pin "2") (pinfunction "2_2") (pintype "passive"))
      (node (ref "C6") (pin "2") (pinfunction "2_2") (pintype "passive"))
      (node (ref "D2") (pin "2") (pinfunction "K_2") (pintype "passive"))
      (node (ref "D3") (pin "1") (pinfunction "A_1") (pintype "passive"))
      (node (ref "D4") (pin "2") (pinfunction "K_2") (pintype "passive"))
      (node (ref "J1") (pin "5") (pinfunction "5_5") (pintype "passive"))
      (node (ref "L3") (pin "2") (pinfunction "2_2") (pintype "passive"))
      (node (ref "P1") (pin "1") (pinfunction "1_1") (pintype "passive"))
      (node (ref "P10") (pin "10") (pinfunction "10_10") (pintype "passive"))
      (node (ref "P10") (pin "2") (pinfunction "2_2") (pintype "passive"))
      (node (ref "P13") (pin "1") (pinfunction "1_1") (pintype "passive"))
      (node (ref "P2") (pin "1") (pinfunction "1_1") (pintype "passive"))
      (node (ref "P3") (pin "9") (pinfunction "9_9") (pintype "passive"))
      (node (ref "P4") (pin "2") (pinfunction "2_2") (pintype "passive"))
      (node (ref "P5") (pin "34") (pinfunction "34_34") (pintype "passive"))
      (node (ref "P6") (pin "34") (pinfunction "34_34") (pintype "passive"))
      (node (ref "P7") (pin "1") (pinfunction "1_1") (pintype "passive"))
      (node (ref "P9") (pin "1") (pinfunction "1_1") (pintype "passive"))
      (node (ref "Q1") (pin "2") (pinfunction "E_2") (pintype "passive"))
      (node (ref "Q2") (pin "2") (pinfunction "E_2") (pintype "passive"))
      (node (ref "Q3") (pin "2") (pinfunction "E_2") (pintype "passive"))
      (node (ref "Q4") (pin "2") (pinfunction "E_2") (pintype "passive"))
      (node (ref "R10") (pin "2") (pinfunction "2_2") (pintype "passive"))
      (node (ref "R7") (pin "2") (pinfunction "2_2") (pintype "passive"))
      (node (ref "R8") (pin "2") (pinfunction "2_2") (pintype "passive"))
      (node (ref "R9") (pin "2") (pinfunction "2_2") (pintype "passive"))
      (node (ref "S6") (pin "1") (pinfunction "COMMON_1") (pintype "passive"))
      (node (ref "U1") (pin "3") (pinfunction "GND_3") (pintype "power_in"))
      (node (ref "U1") (pin "5") (pinfunction "~{ON}/OFF_5") (pintype "input"))
      (node (ref "U2") (pin "1") (pinfunction "~{OE}1_1") (pintype "input"))
      (node (ref "U2") (pin "10") (pinfunction "GND_10") (pintype "power_in"))
      (node (ref "U2") (pin "19") (pinfunction "~{OE}2_19") (pintype "input"))
      (node (ref "U3") (pin "1") (pinfunction "~{CS}_1") (pintype "input"))
      (node (ref "U3") (pin "10") (pinfunction "DGND_10") (pintype "power_in"))
      (node (ref "U3") (pin "2") (pinfunction "~{RD}_2") (pintype "input"))
      (node (ref "U3") (pin "7") (pinfunction "IN_-_7") (pintype "input"))
      (node (ref "U4") (pin "15") (pinfunction "GND_15") (pintype "power_in"))
      (node (ref "U5") (pin "1") (pinfunction "~{OE}1_1") (pintype "input"))
      (node (ref "U5") (pin "10") (pinfunction "GND_10") (pintype "power_in"))
      (node (ref "U5") (pin "19") (pinfunction "~{OE}2_19") (pintype "input"))
      (node (ref "U6") (pin "108") (pinfunction "GND_108") (pintype "power_in"))
      (node (ref "U6") (pin "114") (pinfunction "GND_114") (pintype "power_in"))
      (node (ref "U6") (pin "123") (pinfunction "GND_123") (pintype "power_in"))
      (node (ref "U6") (pin "144") (pinfunction "GND_144") (pintype "power_in"))
      (node (ref "U6") (pin "18") (pinfunction "GND_18") (pintype "power_in"))
      (node (ref "U6") (pin "29") (pinfunction "GND_29") (pintype "power_in"))
      (node (ref "U6") (pin "36") (pinfunction "GND_36") (pintype "power_in"))
      (node (ref "U6") (pin "47") (pinfunction "GND_47") (pintype "power_in"))
      (node (ref "U6") (pin "62") (pinfunction "GND_62") (pintype "power_in"))
      (node (ref "U6") (pin "72") (pinfunction "GND_72") (pintype "power_in"))
      (node (ref "U6") (pin "89") (pinfunction "GND_89") (pintype "power_in"))
      (node (ref "U6") (pin "90") (pinfunction "GND_90") (pintype "power_in"))
      (node (ref "U6") (pin "99") (pinfunction "GND_99") (pintype "power_in"))
      (node (ref "U7") (pin "9") (pinfunction "GND_9") (pintype "power_in"))
      (node (ref "ld1") (pin "1") (pinfunction "gnd_1") (pintype "passive"))
    )
    (net (code "145") (name "Net-(C7-Pad1)") (class "Default")
      (node (ref "C7") (pin "1") (pinfunction "1_1") (pintype "passive"))
      (node (ref "R7") (pin "1") (pinfunction "1_1") (pintype "passive"))
      (node (ref "S2") (pin "1") (pinfunction "1_1") (pintype "passive"))
    )
    (net (code "146") (name "Net-(D1-A)") (class "Default")
      (node (ref "D1") (pin "1") (pinfunction "A_1") (pintype "passive"))
      (node (ref "S1") (pin "2") (pinfunction "NO_2") (pintype "passive"))
    )
    (net (code "147") (name "Net-(D1-K)") (class "Default")
      (node (ref "C1") (pin "1") (pinfunction "1_1") (pintype "passive"))
      (node (ref "D1") (pin "2") (pinfunction "K_2") (pintype "passive"))
      (node (ref "U1") (pin "1") (pinfunction "VIN_1") (pintype "power_in"))
    )
    (net (code "148") (name "Net-(D2-A)") (class "Default")
      (node (ref "D2") (pin "1") (pinfunction "A_1") (pintype "passive"))
      (node (ref "R1") (pin "1") (pinfunction "1_1") (pintype "passive"))
    )
    (net (code "149") (name "Net-(D3-K)") (class "Default")
      (node (ref "D3") (pin "2") (pinfunction "K_2") (pintype "passive"))
      (node (ref "L1") (pin "1") (pinfunction "1_1") (pintype "passive"))
      (node (ref "U1") (pin "2") (pinfunction "OUT_2") (pintype "power_in"))
    )
    (net (code "150") (name "Net-(D4-A)") (class "Default")
      (node (ref "D4") (pin "1") (pinfunction "A_1") (pintype "passive"))
      (node (ref "R6") (pin "1") (pinfunction "1_1") (pintype "passive"))
    )
    (net (code "151") (name "Net-(D5-K)") (class "Default")
      (node (ref "D5") (pin "2") (pinfunction "K_2") (pintype "passive"))
      (node (ref "P3") (pin "8") (pinfunction "8_8") (pintype "passive"))
    )
    (net (code "152") (name "Net-(D6-K)") (class "Default")
      (node (ref "D6") (pin "2") (pinfunction "K_2") (pintype "passive"))
      (node (ref "P3") (pin "7") (pinfunction "7_7") (pintype "passive"))
    )
    (net (code "153") (name "Net-(D7-K)") (class "Default")
      (node (ref "D7") (pin "2") (pinfunction "K_2") (pintype "passive"))
      (node (ref "P3") (pin "6") (pinfunction "6_6") (pintype "passive"))
    )
    (net (code "154") (name "Net-(D8-K)") (class "Default")
      (node (ref "D8") (pin "2") (pinfunction "K_2") (pintype "passive"))
      (node (ref "P3") (pin "5") (pinfunction "5_5") (pintype "passive"))
    )
    (net (code "155") (name "Net-(D9-K)") (class "Default")
      (node (ref "D9") (pin "2") (pinfunction "K_2") (pintype "passive"))
      (node (ref "P3") (pin "4") (pinfunction "4_4") (pintype "passive"))
    )
    (net (code "156") (name "Net-(D10-K)") (class "Default")
      (node (ref "D10") (pin "2") (pinfunction "K_2") (pintype "passive"))
      (node (ref "P3") (pin "3") (pinfunction "3_3") (pintype "passive"))
    )
    (net (code "157") (name "Net-(D11-K)") (class "Default")
      (node (ref "D11") (pin "2") (pinfunction "K_2") (pintype "passive"))
      (node (ref "P3") (pin "2") (pinfunction "2_2") (pintype "passive"))
    )
    (net (code "158") (name "Net-(D12-K)") (class "Default")
      (node (ref "D12") (pin "2") (pinfunction "K_2") (pintype "passive"))
      (node (ref "P3") (pin "1") (pinfunction "1_1") (pintype "passive"))
    )
    (net (code "159") (name "Net-(D13-A)") (class "Default")
      (node (ref "D13") (pin "1") (pinfunction "A_1") (pintype "passive"))
      (node (ref "R20") (pin "1") (pinfunction "1_1") (pintype "passive"))
    )
    (net (code "160") (name "Net-(D13-K)") (class "Default")
      (node (ref "D13") (pin "2") (pinfunction "K_2") (pintype "passive"))
      (node (ref "K1") (pin "5") (pinfunction "T2_5") (pintype "passive"))
      (node (ref "U7") (pin "14") (pinfunction "OUT5_14") (pintype "open_collector"))
    )
    (net (code "161") (name "Net-(D14-A)") (class "Default")
      (node (ref "D14") (pin "1") (pinfunction "A_1") (pintype "passive"))
      (node (ref "R21") (pin "1") (pinfunction "1_1") (pintype "passive"))
    )
    (net (code "162") (name "Net-(D14-K)") (class "Default")
      (node (ref "D14") (pin "2") (pinfunction "K_2") (pintype "passive"))
      (node (ref "K2") (pin "5") (pinfunction "T2_5") (pintype "passive"))
      (node (ref "U7") (pin "13") (pinfunction "OUT6_13") (pintype "open_collector"))
    )
    (net (code "163") (name "Net-(K1-COM)") (class "Default")
      (node (ref "K1") (pin "1") (pinfunction "COM_1") (pintype "passive"))
      (node (ref "P11") (pin "2") (pinfunction "2_2") (pintype "passive"))
    )
    (net (code "164") (name "Net-(K1-NC)") (class "Default")
      (node (ref "K1") (pin "2") (pinfunction "NC_2") (pintype "passive"))
      (node (ref "P11") (pin "1") (pinfunction "1_1") (pintype "passive"))
    )
    (net (code "165") (name "Net-(K1-NO)") (class "Default")
      (node (ref "K1") (pin "3") (pinfunction "NO_3") (pintype "passive"))
      (node (ref "P11") (pin "3") (pinfunction "3_3") (pintype "passive"))
    )
    (net (code "166") (name "Net-(K2-COM)") (class "Default")
      (node (ref "K2") (pin "1") (pinfunction "COM_1") (pintype "passive"))
      (node (ref "P12") (pin "2") (pinfunction "2_2") (pintype "passive"))
    )
    (net (code "167") (name "Net-(K2-NC)") (class "Default")
      (node (ref "K2") (pin "2") (pinfunction "NC_2") (pintype "passive"))
      (node (ref "P12") (pin "1") (pinfunction "1_1") (pintype "passive"))
    )
    (net (code "168") (name "Net-(K2-NO)") (class "Default")
      (node (ref "K2") (pin "3") (pinfunction "NO_3") (pintype "passive"))
      (node (ref "P12") (pin "3") (pinfunction "3_3") (pintype "passive"))
    )
    (net (code "169") (name "Net-(Q1-B)") (class "Default")
      (node (ref "Q1") (pin "1") (pinfunction "B_1") (pintype "passive"))
      (node (ref "R2") (pin "1") (pinfunction "1_1") (pintype "passive"))
    )
    (net (code "170") (name "Net-(Q2-B)") (class "Default")
      (node (ref "Q2") (pin "1") (pinfunction "B_1") (pintype "passive"))
      (node (ref "R3") (pin "1") (pinfunction "1_1") (pintype "passive"))
    )
    (net (code "171") (name "Net-(Q3-B)") (class "Default")
      (node (ref "Q3") (pin "1") (pinfunction "B_1") (pintype "passive"))
      (node (ref "R4") (pin "1") (pinfunction "1_1") (pintype "passive"))
    )
    (net (code "172") (name "Net-(Q4-B)") (class "Default")
      (node (ref "Q4") (pin "1") (pinfunction "B_1") (pintype "passive"))
      (node (ref "R5") (pin "1") (pinfunction "1_1") (pintype "passive"))
    )
    (net (code "173") (name "Net-(S1-COMMON)") (class "Default")
      (node (ref "P1") (pin "2") (pinfunction "2_2") (pintype "passive"))
      (node (ref "S1") (pin "1") (pinfunction "COMMON_1") (pintype "passive"))
    )
    (net (code "174") (name "Net-(U3-AGND)") (class "Default")
      (node (ref "L3") (pin "1") (pinfunction "1_1") (pintype "passive"))
      (node (ref "U3") (pin "8") (pinfunction "AGND_8") (pintype "power_in"))
    )
    (net (code "175") (name "Net-(U3-CLKOUT)") (class "Default")
      (node (ref "R15") (pin "1") (pinfunction "1_1") (pintype "passive"))
      (node (ref "U3") (pin "19") (pinfunction "CLKOUT_19") (pintype "output"))
    )
    (net (code "176") (name "Net-(U3-CLK_IN)") (class "Default")
      (node (ref "C23") (pin "1") (pinfunction "1_1") (pintype "passive"))
      (node (ref "R15") (pin "2") (pinfunction "2_2") (pintype "passive"))
      (node (ref "U3") (pin "4") (pinfunction "CLK_IN_4") (pintype "input"))
    )
    (net (code "177") (name "Net-(U3-DB0)") (class "Default")
      (node (ref "R11") (pin "2") (pinfunction "2_2") (pintype "passive"))
      (node (ref "U3") (pin "18") (pinfunction "DB0_18") (pintype "tri_state"))
    )
    (net (code "178") (name "Net-(U3-DB1)") (class "Default")
      (node (ref "R12") (pin "2") (pinfunction "2_2") (pintype "passive"))
      (node (ref "U3") (pin "17") (pinfunction "DB1_17") (pintype "tri_state"))
    )
    (net (code "179") (name "Net-(U3-DB2)") (class "Default")
      (node (ref "R13") (pin "2") (pinfunction "2_2") (pintype "passive"))
      (node (ref "U3") (pin "16") (pinfunction "DB2_16") (pintype "tri_state"))
    )
    (net (code "180") (name "Net-(U3-DB3)") (class "Default")
      (node (ref "R14") (pin "2") (pinfunction "2_2") (pintype "passive"))
      (node (ref "U3") (pin "15") (pinfunction "DB3_15") (pintype "tri_state"))
    )
    (net (code "181") (name "Net-(U3-DB4)") (class "Default")
      (node (ref "R16") (pin "2") (pinfunction "2_2") (pintype "passive"))
      (node (ref "U3") (pin "14") (pinfunction "DB4_14") (pintype "tri_state"))
    )
    (net (code "182") (name "Net-(U3-DB5)") (class "Default")
      (node (ref "R17") (pin "2") (pinfunction "2_2") (pintype "passive"))
      (node (ref "U3") (pin "13") (pinfunction "DB5_13") (pintype "tri_state"))
    )
    (net (code "183") (name "Net-(U3-DB6)") (class "Default")
      (node (ref "R18") (pin "2") (pinfunction "2_2") (pintype "passive"))
      (node (ref "U3") (pin "12") (pinfunction "DB6_12") (pintype "tri_state"))
    )
    (net (code "184") (name "Net-(U3-DB7)") (class "Default")
      (node (ref "R19") (pin "2") (pinfunction "2_2") (pintype "passive"))
      (node (ref "U3") (pin "11") (pinfunction "DB7_11") (pintype "tri_state"))
    )
    (net (code "185") (name "Net-(U3-IN+)") (class "Default")
      (node (ref "C25") (pin "1") (pinfunction "1_1") (pintype "passive"))
      (node (ref "P4") (pin "1") (pinfunction "1_1") (pintype "passive"))
      (node (ref "U3") (pin "6") (pinfunction "IN+_6") (pintype "input"))
    )
    (net (code "186") (name "Net-(U3-REF{slash}2)") (class "Default")
      (node (ref "C24") (pin "1") (pinfunction "1_1") (pintype "passive"))
      (node (ref "U3") (pin "9") (pinfunction "REF/2_9") (pintype "passive"))
    )
    (net (code "187") (name "Net-(U3-VCC)") (class "Default")
      (node (ref "C22") (pin "1") (pinfunction "1_1") (pintype "passive"))
      (node (ref "L2") (pin "1") (pinfunction "1_1") (pintype "passive"))
      (node (ref "U3") (pin "20") (pinfunction "VCC_20") (pintype "power_in"))
    )
    (net (code "188") (name "Net-(U4-C1+)") (class "Default")
      (node (ref "C26") (pin "1") (pinfunction "1_1") (pintype "passive"))
      (node (ref "U4") (pin "1") (pinfunction "C1+_1") (pintype "passive"))
    )
    (net (code "189") (name "Net-(U4-C1-)") (class "Default")
      (node (ref "C26") (pin "2") (pinfunction "2_2") (pintype "passive"))
      (node (ref "U4") (pin "3") (pinfunction "C1-_3") (pintype "passive"))
    )
    (net (code "190") (name "Net-(U4-C2+)") (class "Default")
      (node (ref "C29") (pin "1") (pinfunction "1_1") (pintype "passive"))
      (node (ref "U4") (pin "4") (pinfunction "C2+_4") (pintype "passive"))
    )
    (net (code "191") (name "Net-(U4-C2-)") (class "Default")
      (node (ref "C29") (pin "2") (pinfunction "2_2") (pintype "passive"))
      (node (ref "U4") (pin "5") (pinfunction "C2-_5") (pintype "passive"))
    )
    (net (code "192") (name "Net-(U4-R1IN)") (class "Default")
      (node (ref "J1") (pin "2") (pinfunction "2_2") (pintype "passive"))
      (node (ref "U4") (pin "13") (pinfunction "R1IN_13") (pintype "input"))
    )
    (net (code "193") (name "Net-(U4-T1OUT)") (class "Default")
      (node (ref "J1") (pin "3") (pinfunction "3_3") (pintype "passive"))
      (node (ref "U4") (pin "14") (pinfunction "T1OUT_14") (pintype "output"))
    )
    (net (code "194") (name "Net-(U4-V+)") (class "Default")
      (node (ref "C28") (pin "1") (pinfunction "1_1") (pintype "passive"))
      (node (ref "U4") (pin "2") (pinfunction "V+_2") (pintype "power_in"))
    )
    (net (code "195") (name "Net-(U4-V-)") (class "Default")
      (node (ref "C31") (pin "2") (pinfunction "2_2") (pintype "passive"))
      (node (ref "U4") (pin "6") (pinfunction "V-_6") (pintype "power_in"))
    )
    (net (code "196") (name "Net-(U7-OUT1)") (class "Default")
      (node (ref "P8") (pin "1") (pinfunction "1_1") (pintype "passive"))
      (node (ref "U7") (pin "18") (pinfunction "OUT1_18") (pintype "open_collector"))
    )
    (net (code "197") (name "Net-(U7-OUT2)") (class "Default")
      (node (ref "P8") (pin "2") (pinfunction "2_2") (pintype "passive"))
      (node (ref "U7") (pin "17") (pinfunction "OUT2_17") (pintype "open_collector"))
    )
    (net (code "198") (name "Net-(U7-OUT3)") (class "Default")
      (node (ref "P8") (pin "3") (pinfunction "3_3") (pintype "passive"))
      (node (ref "U7") (pin "16") (pinfunction "OUT3_16") (pintype "open_collector"))
    )
    (net (code "199") (name "Net-(U7-OUT4)") (class "Default")
      (node (ref "P8") (pin "4") (pinfunction "4_4") (pintype "passive"))
      (node (ref "U7") (pin "15") (pinfunction "OUT4_15") (pintype "open_collector"))
    )
    (net (code "200") (name "Net-(U7-OUT7)") (class "Default")
      (node (ref "LS1") (pin "2") (pinfunction "2_2") (pintype "passive"))
      (node (ref "U7") (pin "12") (pinfunction "OUT7_12") (pintype "open_collector"))
    )
    (net (code "201") (name "Net-(U7-OUT8)") (class "Default")
      (node (ref "P14") (pin "2") (pinfunction "2_2") (pintype "passive"))
      (node (ref "U7") (pin "11") (pinfunction "OUT8_11") (pintype "open_collector"))
    )
    (net (code "202") (name "unconnected-(*1-E{slash}D-Pad1)") (class "Default")
      (node (ref "*1") (pin "1") (pinfunction "E/D_1") (pintype "passive+no_connect"))
    )
    (net (code "203") (name "unconnected-(J1-MH1-Pad10)") (class "Default")
      (node (ref "J1") (pin "10") (pinfunction "MH1_10") (pintype "passive+no_connect"))
    )
    (net (code "204") (name "unconnected-(J1-MH2-Pad11)") (class "Default")
      (node (ref "J1") (pin "11") (pinfunction "MH2_11") (pintype "passive+no_connect"))
    )
    (net (code "205") (name "unconnected-(J1-Pad1)") (class "Default")
      (node (ref "J1") (pin "1") (pinfunction "1_1") (pintype "passive+no_connect"))
    )
    (net (code "206") (name "unconnected-(J1-Pad4)") (class "Default")
      (node (ref "J1") (pin "4") (pinfunction "4_4") (pintype "passive+no_connect"))
    )
    (net (code "207") (name "unconnected-(J1-Pad6)") (class "Default")
      (node (ref "J1") (pin "6") (pinfunction "6_6") (pintype "passive+no_connect"))
    )
    (net (code "208") (name "unconnected-(J1-Pad7)") (class "Default")
      (node (ref "J1") (pin "7") (pinfunction "7_7") (pintype "passive+no_connect"))
    )
    (net (code "209") (name "unconnected-(J1-Pad8)") (class "Default")
      (node (ref "J1") (pin "8") (pinfunction "8_8") (pintype "passive+no_connect"))
    )
    (net (code "210") (name "unconnected-(J1-Pad9)") (class "Default")
      (node (ref "J1") (pin "9") (pinfunction "9_9") (pintype "passive+no_connect"))
    )
    (net (code "211") (name "unconnected-(L2-Pad2)") (class "Default")
      (node (ref "L2") (pin "2") (pinfunction "2_2") (pintype "passive"))
    )
    (net (code "212") (name "unconnected-(P10-Pad6)") (class "Default")
      (node (ref "P10") (pin "6") (pinfunction "6_6") (pintype "passive+no_connect"))
    )
    (net (code "213") (name "unconnected-(P10-Pad7)") (class "Default")
      (node (ref "P10") (pin "7") (pinfunction "7_7") (pintype "passive+no_connect"))
    )
    (net (code "214") (name "unconnected-(P10-Pad8)") (class "Default")
      (node (ref "P10") (pin "8") (pinfunction "8_8") (pintype "passive+no_connect"))
    )
    (net (code "215") (name "unconnected-(U4-R2IN-Pad8)") (class "Default")
      (node (ref "U4") (pin "8") (pinfunction "R2IN_8") (pintype "input+no_connect"))
    )
    (net (code "216") (name "unconnected-(U4-R2OUT-Pad9)") (class "Default")
      (node (ref "U4") (pin "9") (pinfunction "R2OUT_9") (pintype "output+no_connect"))
    )
    (net (code "217") (name "unconnected-(U4-T2IN-Pad10)") (class "Default")
      (node (ref "U4") (pin "10") (pinfunction "T2IN_10") (pintype "input+no_connect"))
    )
    (net (code "218") (name "unconnected-(U4-T2OUT-Pad7)") (class "Default")
      (node (ref "U4") (pin "7") (pinfunction "T2OUT_7") (pintype "output+no_connect"))
    )
  )
)
